# 11-de-7.net
KiCad netlist of a schematic drawn in EAGLE
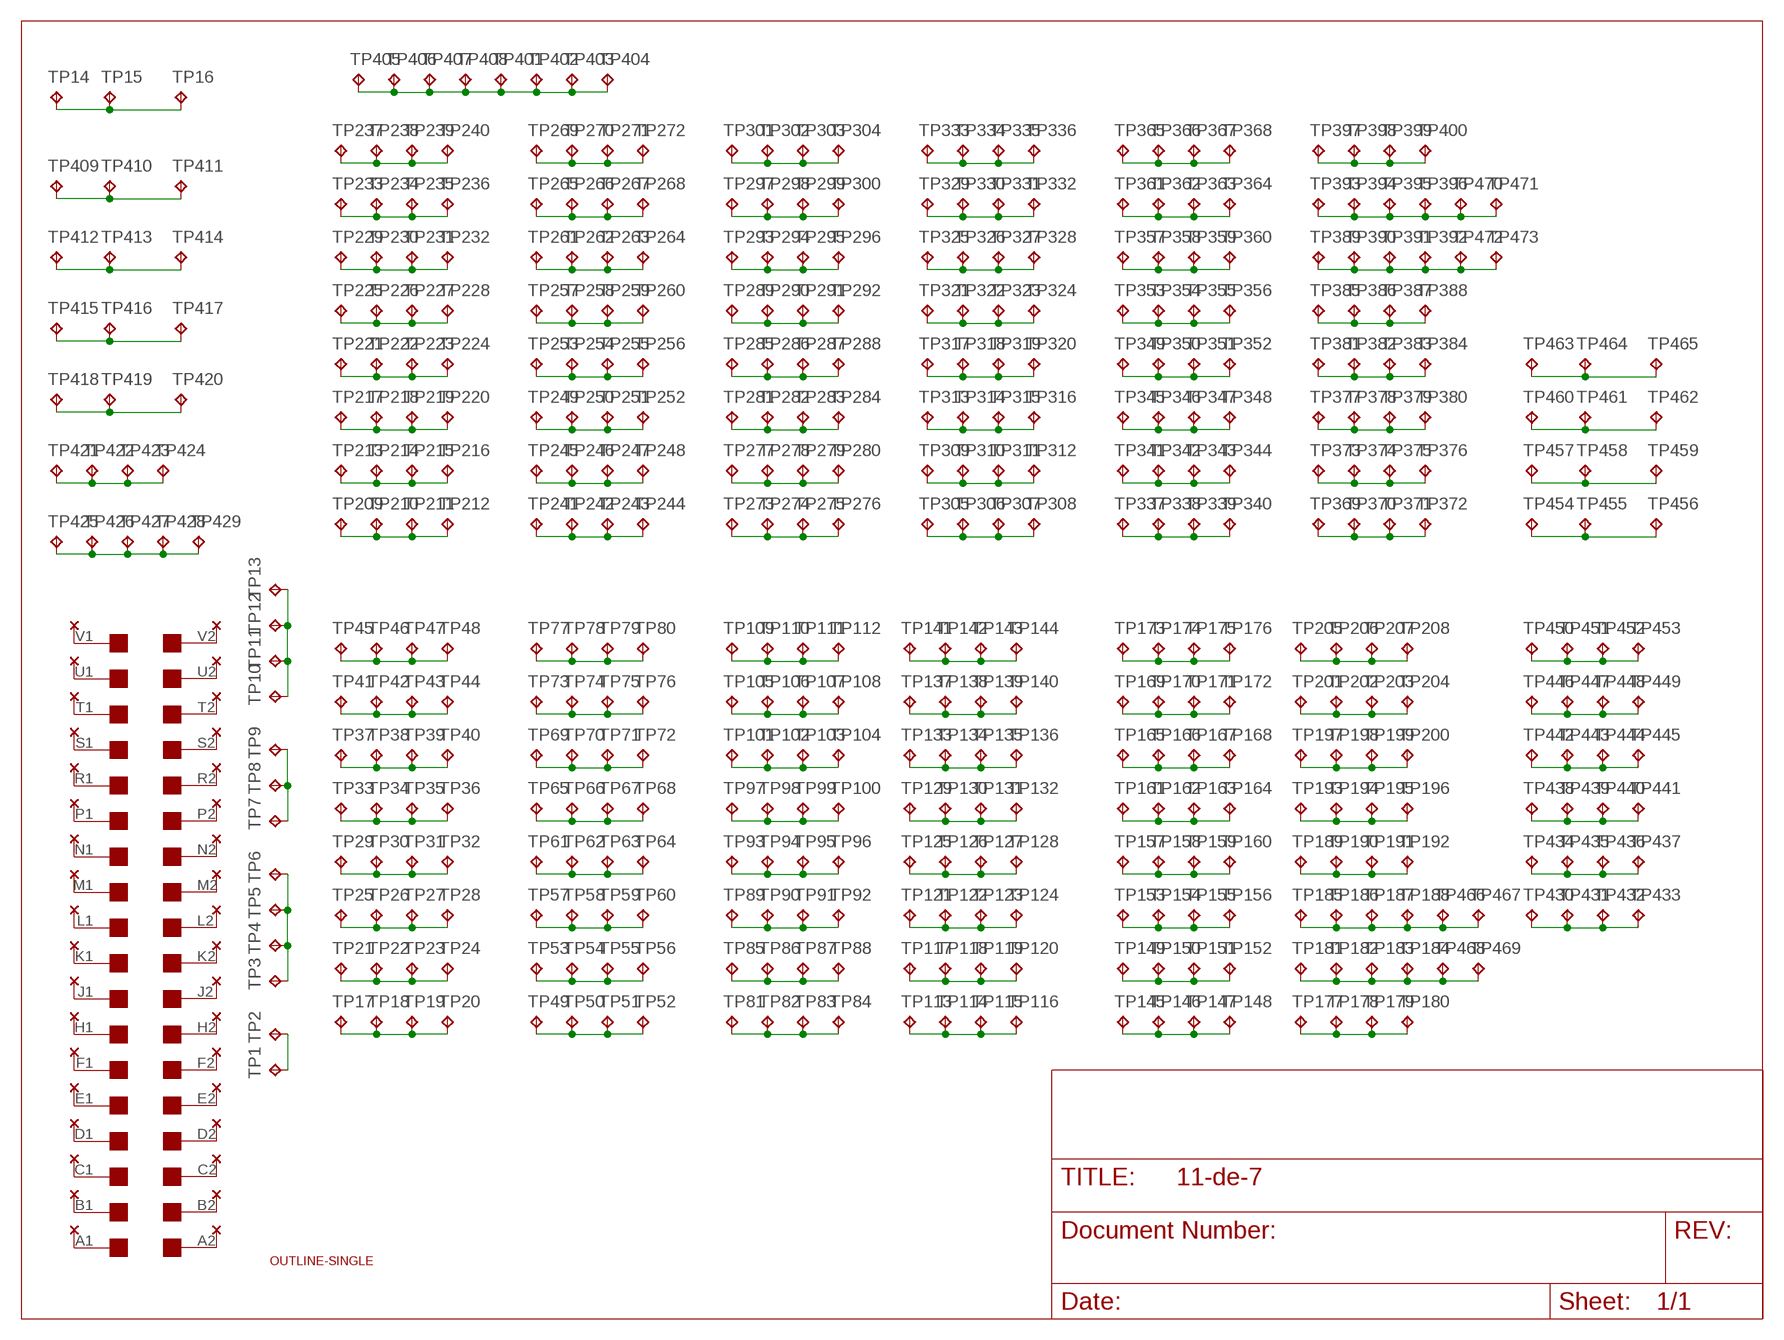
[diagram p0: schematic, sheet 1]

(export (version "E")
  (design (tool "Eeschema 10.0.6"))
  (components
    (comp (ref "TP1")
      (value "TPPAD1-13Y")
      (footprint "eagle-import:P1-13Y")
      (libsource (lib "eagle-import") (part "TPPAD1-13Y"))
    )
    (comp (ref "TP2")
      (value "TPPAD1-13")
      (footprint "eagle-import:P1-13")
      (libsource (lib "eagle-import") (part "TPPAD1-13"))
    )
    (comp (ref "TP3")
      (value "TPPAD1-13Y")
      (footprint "eagle-import:P1-13Y")
      (libsource (lib "eagle-import") (part "TPPAD1-13Y"))
    )
    (comp (ref "TP4")
      (value "TPPAD1-13Y")
      (footprint "eagle-import:P1-13Y")
      (libsource (lib "eagle-import") (part "TPPAD1-13Y"))
    )
    (comp (ref "TP5")
      (value "TPPAD1-13Y")
      (footprint "eagle-import:P1-13Y")
      (libsource (lib "eagle-import") (part "TPPAD1-13Y"))
    )
    (comp (ref "TP6")
      (value "TPPAD1-13Y")
      (footprint "eagle-import:P1-13Y")
      (libsource (lib "eagle-import") (part "TPPAD1-13Y"))
    )
    (comp (ref "TP7")
      (value "TPPAD1-13Y")
      (footprint "eagle-import:P1-13Y")
      (libsource (lib "eagle-import") (part "TPPAD1-13Y"))
    )
    (comp (ref "TP8")
      (value "TPPAD1-13Y")
      (footprint "eagle-import:P1-13Y")
      (libsource (lib "eagle-import") (part "TPPAD1-13Y"))
    )
    (comp (ref "TP9")
      (value "TPPAD1-13Y")
      (footprint "eagle-import:P1-13Y")
      (libsource (lib "eagle-import") (part "TPPAD1-13Y"))
    )
    (comp (ref "TP10")
      (value "TPPAD1-13Y")
      (footprint "eagle-import:P1-13Y")
      (libsource (lib "eagle-import") (part "TPPAD1-13Y"))
    )
    (comp (ref "TP11")
      (value "TPPAD1-13Y")
      (footprint "eagle-import:P1-13Y")
      (libsource (lib "eagle-import") (part "TPPAD1-13Y"))
    )
    (comp (ref "TP12")
      (value "TPPAD1-13Y")
      (footprint "eagle-import:P1-13Y")
      (libsource (lib "eagle-import") (part "TPPAD1-13Y"))
    )
    (comp (ref "TP13")
      (value "TPPAD1-13Y")
      (footprint "eagle-import:P1-13Y")
      (libsource (lib "eagle-import") (part "TPPAD1-13Y"))
    )
    (comp (ref "TP14")
      (value "TPPAD1-13Y")
      (footprint "eagle-import:P1-13Y")
      (libsource (lib "eagle-import") (part "TPPAD1-13Y"))
    )
    (comp (ref "TP15")
      (value "TPPAD1-13Y")
      (footprint "eagle-import:P1-13Y")
      (libsource (lib "eagle-import") (part "TPPAD1-13Y"))
    )
    (comp (ref "TP16")
      (value "TPPAD1-13Y")
      (footprint "eagle-import:P1-13Y")
      (libsource (lib "eagle-import") (part "TPPAD1-13Y"))
    )
    (comp (ref "TP17")
      (value "TPPAD1-13Y")
      (footprint "eagle-import:P1-13Y")
      (libsource (lib "eagle-import") (part "TPPAD1-13Y"))
    )
    (comp (ref "TP18")
      (value "TPPAD1-13Y")
      (footprint "eagle-import:P1-13Y")
      (libsource (lib "eagle-import") (part "TPPAD1-13Y"))
    )
    (comp (ref "TP19")
      (value "TPPAD1-13Y")
      (footprint "eagle-import:P1-13Y")
      (libsource (lib "eagle-import") (part "TPPAD1-13Y"))
    )
    (comp (ref "TP20")
      (value "TPPAD1-13Y")
      (footprint "eagle-import:P1-13Y")
      (libsource (lib "eagle-import") (part "TPPAD1-13Y"))
    )
    (comp (ref "TP21")
      (value "TPPAD1-13Y")
      (footprint "eagle-import:P1-13Y")
      (libsource (lib "eagle-import") (part "TPPAD1-13Y"))
    )
    (comp (ref "TP22")
      (value "TPPAD1-13Y")
      (footprint "eagle-import:P1-13Y")
      (libsource (lib "eagle-import") (part "TPPAD1-13Y"))
    )
    (comp (ref "TP23")
      (value "TPPAD1-13Y")
      (footprint "eagle-import:P1-13Y")
      (libsource (lib "eagle-import") (part "TPPAD1-13Y"))
    )
    (comp (ref "TP24")
      (value "TPPAD1-13Y")
      (footprint "eagle-import:P1-13Y")
      (libsource (lib "eagle-import") (part "TPPAD1-13Y"))
    )
    (comp (ref "TP25")
      (value "TPPAD1-13Y")
      (footprint "eagle-import:P1-13Y")
      (libsource (lib "eagle-import") (part "TPPAD1-13Y"))
    )
    (comp (ref "TP26")
      (value "TPPAD1-13Y")
      (footprint "eagle-import:P1-13Y")
      (libsource (lib "eagle-import") (part "TPPAD1-13Y"))
    )
    (comp (ref "TP27")
      (value "TPPAD1-13Y")
      (footprint "eagle-import:P1-13Y")
      (libsource (lib "eagle-import") (part "TPPAD1-13Y"))
    )
    (comp (ref "TP28")
      (value "TPPAD1-13Y")
      (footprint "eagle-import:P1-13Y")
      (libsource (lib "eagle-import") (part "TPPAD1-13Y"))
    )
    (comp (ref "TP29")
      (value "TPPAD1-13Y")
      (footprint "eagle-import:P1-13Y")
      (libsource (lib "eagle-import") (part "TPPAD1-13Y"))
    )
    (comp (ref "TP30")
      (value "TPPAD1-13Y")
      (footprint "eagle-import:P1-13Y")
      (libsource (lib "eagle-import") (part "TPPAD1-13Y"))
    )
    (comp (ref "TP31")
      (value "TPPAD1-13Y")
      (footprint "eagle-import:P1-13Y")
      (libsource (lib "eagle-import") (part "TPPAD1-13Y"))
    )
    (comp (ref "TP32")
      (value "TPPAD1-13Y")
      (footprint "eagle-import:P1-13Y")
      (libsource (lib "eagle-import") (part "TPPAD1-13Y"))
    )
    (comp (ref "TP33")
      (value "TPPAD1-13Y")
      (footprint "eagle-import:P1-13Y")
      (libsource (lib "eagle-import") (part "TPPAD1-13Y"))
    )
    (comp (ref "TP34")
      (value "TPPAD1-13Y")
      (footprint "eagle-import:P1-13Y")
      (libsource (lib "eagle-import") (part "TPPAD1-13Y"))
    )
    (comp (ref "TP35")
      (value "TPPAD1-13Y")
      (footprint "eagle-import:P1-13Y")
      (libsource (lib "eagle-import") (part "TPPAD1-13Y"))
    )
    (comp (ref "TP36")
      (value "TPPAD1-13Y")
      (footprint "eagle-import:P1-13Y")
      (libsource (lib "eagle-import") (part "TPPAD1-13Y"))
    )
    (comp (ref "TP37")
      (value "TPPAD1-13Y")
      (footprint "eagle-import:P1-13Y")
      (libsource (lib "eagle-import") (part "TPPAD1-13Y"))
    )
    (comp (ref "TP38")
      (value "TPPAD1-13Y")
      (footprint "eagle-import:P1-13Y")
      (libsource (lib "eagle-import") (part "TPPAD1-13Y"))
    )
    (comp (ref "TP39")
      (value "TPPAD1-13Y")
      (footprint "eagle-import:P1-13Y")
      (libsource (lib "eagle-import") (part "TPPAD1-13Y"))
    )
    (comp (ref "TP40")
      (value "TPPAD1-13Y")
      (footprint "eagle-import:P1-13Y")
      (libsource (lib "eagle-import") (part "TPPAD1-13Y"))
    )
    (comp (ref "TP41")
      (value "TPPAD1-13Y")
      (footprint "eagle-import:P1-13Y")
      (libsource (lib "eagle-import") (part "TPPAD1-13Y"))
    )
    (comp (ref "TP42")
      (value "TPPAD1-13Y")
      (footprint "eagle-import:P1-13Y")
      (libsource (lib "eagle-import") (part "TPPAD1-13Y"))
    )
    (comp (ref "TP43")
      (value "TPPAD1-13Y")
      (footprint "eagle-import:P1-13Y")
      (libsource (lib "eagle-import") (part "TPPAD1-13Y"))
    )
    (comp (ref "TP44")
      (value "TPPAD1-13Y")
      (footprint "eagle-import:P1-13Y")
      (libsource (lib "eagle-import") (part "TPPAD1-13Y"))
    )
    (comp (ref "TP45")
      (value "TPPAD1-13Y")
      (footprint "eagle-import:P1-13Y")
      (libsource (lib "eagle-import") (part "TPPAD1-13Y"))
    )
    (comp (ref "TP46")
      (value "TPPAD1-13Y")
      (footprint "eagle-import:P1-13Y")
      (libsource (lib "eagle-import") (part "TPPAD1-13Y"))
    )
    (comp (ref "TP47")
      (value "TPPAD1-13Y")
      (footprint "eagle-import:P1-13Y")
      (libsource (lib "eagle-import") (part "TPPAD1-13Y"))
    )
    (comp (ref "TP48")
      (value "TPPAD1-13Y")
      (footprint "eagle-import:P1-13Y")
      (libsource (lib "eagle-import") (part "TPPAD1-13Y"))
    )
    (comp (ref "TP49")
      (value "TPPAD1-13Y")
      (footprint "eagle-import:P1-13Y")
      (libsource (lib "eagle-import") (part "TPPAD1-13Y"))
    )
    (comp (ref "TP50")
      (value "TPPAD1-13Y")
      (footprint "eagle-import:P1-13Y")
      (libsource (lib "eagle-import") (part "TPPAD1-13Y"))
    )
    (comp (ref "TP51")
      (value "TPPAD1-13Y")
      (footprint "eagle-import:P1-13Y")
      (libsource (lib "eagle-import") (part "TPPAD1-13Y"))
    )
    (comp (ref "TP52")
      (value "TPPAD1-13Y")
      (footprint "eagle-import:P1-13Y")
      (libsource (lib "eagle-import") (part "TPPAD1-13Y"))
    )
    (comp (ref "TP53")
      (value "TPPAD1-13Y")
      (footprint "eagle-import:P1-13Y")
      (libsource (lib "eagle-import") (part "TPPAD1-13Y"))
    )
    (comp (ref "TP54")
      (value "TPPAD1-13Y")
      (footprint "eagle-import:P1-13Y")
      (libsource (lib "eagle-import") (part "TPPAD1-13Y"))
    )
    (comp (ref "TP55")
      (value "TPPAD1-13Y")
      (footprint "eagle-import:P1-13Y")
      (libsource (lib "eagle-import") (part "TPPAD1-13Y"))
    )
    (comp (ref "TP56")
      (value "TPPAD1-13Y")
      (footprint "eagle-import:P1-13Y")
      (libsource (lib "eagle-import") (part "TPPAD1-13Y"))
    )
    (comp (ref "TP57")
      (value "TPPAD1-13Y")
      (footprint "eagle-import:P1-13Y")
      (libsource (lib "eagle-import") (part "TPPAD1-13Y"))
    )
    (comp (ref "TP58")
      (value "TPPAD1-13Y")
      (footprint "eagle-import:P1-13Y")
      (libsource (lib "eagle-import") (part "TPPAD1-13Y"))
    )
    (comp (ref "TP59")
      (value "TPPAD1-13Y")
      (footprint "eagle-import:P1-13Y")
      (libsource (lib "eagle-import") (part "TPPAD1-13Y"))
    )
    (comp (ref "TP60")
      (value "TPPAD1-13Y")
      (footprint "eagle-import:P1-13Y")
      (libsource (lib "eagle-import") (part "TPPAD1-13Y"))
    )
    (comp (ref "TP61")
      (value "TPPAD1-13Y")
      (footprint "eagle-import:P1-13Y")
      (libsource (lib "eagle-import") (part "TPPAD1-13Y"))
    )
    (comp (ref "TP62")
      (value "TPPAD1-13Y")
      (footprint "eagle-import:P1-13Y")
      (libsource (lib "eagle-import") (part "TPPAD1-13Y"))
    )
    (comp (ref "TP63")
      (value "TPPAD1-13Y")
      (footprint "eagle-import:P1-13Y")
      (libsource (lib "eagle-import") (part "TPPAD1-13Y"))
    )
    (comp (ref "TP64")
      (value "TPPAD1-13Y")
      (footprint "eagle-import:P1-13Y")
      (libsource (lib "eagle-import") (part "TPPAD1-13Y"))
    )
    (comp (ref "TP65")
      (value "TPPAD1-13Y")
      (footprint "eagle-import:P1-13Y")
      (libsource (lib "eagle-import") (part "TPPAD1-13Y"))
    )
    (comp (ref "TP66")
      (value "TPPAD1-13Y")
      (footprint "eagle-import:P1-13Y")
      (libsource (lib "eagle-import") (part "TPPAD1-13Y"))
    )
    (comp (ref "TP67")
      (value "TPPAD1-13Y")
      (footprint "eagle-import:P1-13Y")
      (libsource (lib "eagle-import") (part "TPPAD1-13Y"))
    )
    (comp (ref "TP68")
      (value "TPPAD1-13Y")
      (footprint "eagle-import:P1-13Y")
      (libsource (lib "eagle-import") (part "TPPAD1-13Y"))
    )
    (comp (ref "TP69")
      (value "TPPAD1-13Y")
      (footprint "eagle-import:P1-13Y")
      (libsource (lib "eagle-import") (part "TPPAD1-13Y"))
    )
    (comp (ref "TP70")
      (value "TPPAD1-13Y")
      (footprint "eagle-import:P1-13Y")
      (libsource (lib "eagle-import") (part "TPPAD1-13Y"))
    )
    (comp (ref "TP71")
      (value "TPPAD1-13Y")
      (footprint "eagle-import:P1-13Y")
      (libsource (lib "eagle-import") (part "TPPAD1-13Y"))
    )
    (comp (ref "TP72")
      (value "TPPAD1-13Y")
      (footprint "eagle-import:P1-13Y")
      (libsource (lib "eagle-import") (part "TPPAD1-13Y"))
    )
    (comp (ref "TP73")
      (value "TPPAD1-13Y")
      (footprint "eagle-import:P1-13Y")
      (libsource (lib "eagle-import") (part "TPPAD1-13Y"))
    )
    (comp (ref "TP74")
      (value "TPPAD1-13Y")
      (footprint "eagle-import:P1-13Y")
      (libsource (lib "eagle-import") (part "TPPAD1-13Y"))
    )
    (comp (ref "TP75")
      (value "TPPAD1-13Y")
      (footprint "eagle-import:P1-13Y")
      (libsource (lib "eagle-import") (part "TPPAD1-13Y"))
    )
    (comp (ref "TP76")
      (value "TPPAD1-13Y")
      (footprint "eagle-import:P1-13Y")
      (libsource (lib "eagle-import") (part "TPPAD1-13Y"))
    )
    (comp (ref "TP77")
      (value "TPPAD1-13Y")
      (footprint "eagle-import:P1-13Y")
      (libsource (lib "eagle-import") (part "TPPAD1-13Y"))
    )
    (comp (ref "TP78")
      (value "TPPAD1-13Y")
      (footprint "eagle-import:P1-13Y")
      (libsource (lib "eagle-import") (part "TPPAD1-13Y"))
    )
    (comp (ref "TP79")
      (value "TPPAD1-13Y")
      (footprint "eagle-import:P1-13Y")
      (libsource (lib "eagle-import") (part "TPPAD1-13Y"))
    )
    (comp (ref "TP80")
      (value "TPPAD1-13Y")
      (footprint "eagle-import:P1-13Y")
      (libsource (lib "eagle-import") (part "TPPAD1-13Y"))
    )
    (comp (ref "TP81")
      (value "TPPAD1-13Y")
      (footprint "eagle-import:P1-13Y")
      (libsource (lib "eagle-import") (part "TPPAD1-13Y"))
    )
    (comp (ref "TP82")
      (value "TPPAD1-13Y")
      (footprint "eagle-import:P1-13Y")
      (libsource (lib "eagle-import") (part "TPPAD1-13Y"))
    )
    (comp (ref "TP83")
      (value "TPPAD1-13Y")
      (footprint "eagle-import:P1-13Y")
      (libsource (lib "eagle-import") (part "TPPAD1-13Y"))
    )
    (comp (ref "TP84")
      (value "TPPAD1-13Y")
      (footprint "eagle-import:P1-13Y")
      (libsource (lib "eagle-import") (part "TPPAD1-13Y"))
    )
    (comp (ref "TP85")
      (value "TPPAD1-13Y")
      (footprint "eagle-import:P1-13Y")
      (libsource (lib "eagle-import") (part "TPPAD1-13Y"))
    )
    (comp (ref "TP86")
      (value "TPPAD1-13Y")
      (footprint "eagle-import:P1-13Y")
      (libsource (lib "eagle-import") (part "TPPAD1-13Y"))
    )
    (comp (ref "TP87")
      (value "TPPAD1-13Y")
      (footprint "eagle-import:P1-13Y")
      (libsource (lib "eagle-import") (part "TPPAD1-13Y"))
    )
    (comp (ref "TP88")
      (value "TPPAD1-13Y")
      (footprint "eagle-import:P1-13Y")
      (libsource (lib "eagle-import") (part "TPPAD1-13Y"))
    )
    (comp (ref "TP89")
      (value "TPPAD1-13Y")
      (footprint "eagle-import:P1-13Y")
      (libsource (lib "eagle-import") (part "TPPAD1-13Y"))
    )
    (comp (ref "TP90")
      (value "TPPAD1-13Y")
      (footprint "eagle-import:P1-13Y")
      (libsource (lib "eagle-import") (part "TPPAD1-13Y"))
    )
    (comp (ref "TP91")
      (value "TPPAD1-13Y")
      (footprint "eagle-import:P1-13Y")
      (libsource (lib "eagle-import") (part "TPPAD1-13Y"))
    )
    (comp (ref "TP92")
      (value "TPPAD1-13Y")
      (footprint "eagle-import:P1-13Y")
      (libsource (lib "eagle-import") (part "TPPAD1-13Y"))
    )
    (comp (ref "TP93")
      (value "TPPAD1-13Y")
      (footprint "eagle-import:P1-13Y")
      (libsource (lib "eagle-import") (part "TPPAD1-13Y"))
    )
    (comp (ref "TP94")
      (value "TPPAD1-13Y")
      (footprint "eagle-import:P1-13Y")
      (libsource (lib "eagle-import") (part "TPPAD1-13Y"))
    )
    (comp (ref "TP95")
      (value "TPPAD1-13Y")
      (footprint "eagle-import:P1-13Y")
      (libsource (lib "eagle-import") (part "TPPAD1-13Y"))
    )
    (comp (ref "TP96")
      (value "TPPAD1-13Y")
      (footprint "eagle-import:P1-13Y")
      (libsource (lib "eagle-import") (part "TPPAD1-13Y"))
    )
    (comp (ref "TP97")
      (value "TPPAD1-13Y")
      (footprint "eagle-import:P1-13Y")
      (libsource (lib "eagle-import") (part "TPPAD1-13Y"))
    )
    (comp (ref "TP98")
      (value "TPPAD1-13Y")
      (footprint "eagle-import:P1-13Y")
      (libsource (lib "eagle-import") (part "TPPAD1-13Y"))
    )
    (comp (ref "TP99")
      (value "TPPAD1-13Y")
      (footprint "eagle-import:P1-13Y")
      (libsource (lib "eagle-import") (part "TPPAD1-13Y"))
    )
    (comp (ref "TP100")
      (value "TPPAD1-13Y")
      (footprint "eagle-import:P1-13Y")
      (libsource (lib "eagle-import") (part "TPPAD1-13Y"))
    )
    (comp (ref "TP101")
      (value "TPPAD1-13Y")
      (footprint "eagle-import:P1-13Y")
      (libsource (lib "eagle-import") (part "TPPAD1-13Y"))
    )
    (comp (ref "TP102")
      (value "TPPAD1-13Y")
      (footprint "eagle-import:P1-13Y")
      (libsource (lib "eagle-import") (part "TPPAD1-13Y"))
    )
    (comp (ref "TP103")
      (value "TPPAD1-13Y")
      (footprint "eagle-import:P1-13Y")
      (libsource (lib "eagle-import") (part "TPPAD1-13Y"))
    )
    (comp (ref "TP104")
      (value "TPPAD1-13Y")
      (footprint "eagle-import:P1-13Y")
      (libsource (lib "eagle-import") (part "TPPAD1-13Y"))
    )
    (comp (ref "TP105")
      (value "TPPAD1-13Y")
      (footprint "eagle-import:P1-13Y")
      (libsource (lib "eagle-import") (part "TPPAD1-13Y"))
    )
    (comp (ref "TP106")
      (value "TPPAD1-13Y")
      (footprint "eagle-import:P1-13Y")
      (libsource (lib "eagle-import") (part "TPPAD1-13Y"))
    )
    (comp (ref "TP107")
      (value "TPPAD1-13Y")
      (footprint "eagle-import:P1-13Y")
      (libsource (lib "eagle-import") (part "TPPAD1-13Y"))
    )
    (comp (ref "TP108")
      (value "TPPAD1-13Y")
      (footprint "eagle-import:P1-13Y")
      (libsource (lib "eagle-import") (part "TPPAD1-13Y"))
    )
    (comp (ref "TP109")
      (value "TPPAD1-13Y")
      (footprint "eagle-import:P1-13Y")
      (libsource (lib "eagle-import") (part "TPPAD1-13Y"))
    )
    (comp (ref "TP110")
      (value "TPPAD1-13Y")
      (footprint "eagle-import:P1-13Y")
      (libsource (lib "eagle-import") (part "TPPAD1-13Y"))
    )
    (comp (ref "TP111")
      (value "TPPAD1-13Y")
      (footprint "eagle-import:P1-13Y")
      (libsource (lib "eagle-import") (part "TPPAD1-13Y"))
    )
    (comp (ref "TP112")
      (value "TPPAD1-13Y")
      (footprint "eagle-import:P1-13Y")
      (libsource (lib "eagle-import") (part "TPPAD1-13Y"))
    )
    (comp (ref "TP113")
      (value "TPPAD1-13Y")
      (footprint "eagle-import:P1-13Y")
      (libsource (lib "eagle-import") (part "TPPAD1-13Y"))
    )
    (comp (ref "TP114")
      (value "TPPAD1-13Y")
      (footprint "eagle-import:P1-13Y")
      (libsource (lib "eagle-import") (part "TPPAD1-13Y"))
    )
    (comp (ref "TP115")
      (value "TPPAD1-13Y")
      (footprint "eagle-import:P1-13Y")
      (libsource (lib "eagle-import") (part "TPPAD1-13Y"))
    )
    (comp (ref "TP116")
      (value "TPPAD1-13Y")
      (footprint "eagle-import:P1-13Y")
      (libsource (lib "eagle-import") (part "TPPAD1-13Y"))
    )
    (comp (ref "TP117")
      (value "TPPAD1-13Y")
      (footprint "eagle-import:P1-13Y")
      (libsource (lib "eagle-import") (part "TPPAD1-13Y"))
    )
    (comp (ref "TP118")
      (value "TPPAD1-13Y")
      (footprint "eagle-import:P1-13Y")
      (libsource (lib "eagle-import") (part "TPPAD1-13Y"))
    )
    (comp (ref "TP119")
      (value "TPPAD1-13Y")
      (footprint "eagle-import:P1-13Y")
      (libsource (lib "eagle-import") (part "TPPAD1-13Y"))
    )
    (comp (ref "TP120")
      (value "TPPAD1-13Y")
      (footprint "eagle-import:P1-13Y")
      (libsource (lib "eagle-import") (part "TPPAD1-13Y"))
    )
    (comp (ref "TP121")
      (value "TPPAD1-13Y")
      (footprint "eagle-import:P1-13Y")
      (libsource (lib "eagle-import") (part "TPPAD1-13Y"))
    )
    (comp (ref "TP122")
      (value "TPPAD1-13Y")
      (footprint "eagle-import:P1-13Y")
      (libsource (lib "eagle-import") (part "TPPAD1-13Y"))
    )
    (comp (ref "TP123")
      (value "TPPAD1-13Y")
      (footprint "eagle-import:P1-13Y")
      (libsource (lib "eagle-import") (part "TPPAD1-13Y"))
    )
    (comp (ref "TP124")
      (value "TPPAD1-13Y")
      (footprint "eagle-import:P1-13Y")
      (libsource (lib "eagle-import") (part "TPPAD1-13Y"))
    )
    (comp (ref "TP125")
      (value "TPPAD1-13Y")
      (footprint "eagle-import:P1-13Y")
      (libsource (lib "eagle-import") (part "TPPAD1-13Y"))
    )
    (comp (ref "TP126")
      (value "TPPAD1-13Y")
      (footprint "eagle-import:P1-13Y")
      (libsource (lib "eagle-import") (part "TPPAD1-13Y"))
    )
    (comp (ref "TP127")
      (value "TPPAD1-13Y")
      (footprint "eagle-import:P1-13Y")
      (libsource (lib "eagle-import") (part "TPPAD1-13Y"))
    )
    (comp (ref "TP128")
      (value "TPPAD1-13Y")
      (footprint "eagle-import:P1-13Y")
      (libsource (lib "eagle-import") (part "TPPAD1-13Y"))
    )
    (comp (ref "TP129")
      (value "TPPAD1-13Y")
      (footprint "eagle-import:P1-13Y")
      (libsource (lib "eagle-import") (part "TPPAD1-13Y"))
    )
    (comp (ref "TP130")
      (value "TPPAD1-13Y")
      (footprint "eagle-import:P1-13Y")
      (libsource (lib "eagle-import") (part "TPPAD1-13Y"))
    )
    (comp (ref "TP131")
      (value "TPPAD1-13Y")
      (footprint "eagle-import:P1-13Y")
      (libsource (lib "eagle-import") (part "TPPAD1-13Y"))
    )
    (comp (ref "TP132")
      (value "TPPAD1-13Y")
      (footprint "eagle-import:P1-13Y")
      (libsource (lib "eagle-import") (part "TPPAD1-13Y"))
    )
    (comp (ref "TP133")
      (value "TPPAD1-13Y")
      (footprint "eagle-import:P1-13Y")
      (libsource (lib "eagle-import") (part "TPPAD1-13Y"))
    )
    (comp (ref "TP134")
      (value "TPPAD1-13Y")
      (footprint "eagle-import:P1-13Y")
      (libsource (lib "eagle-import") (part "TPPAD1-13Y"))
    )
    (comp (ref "TP135")
      (value "TPPAD1-13Y")
      (footprint "eagle-import:P1-13Y")
      (libsource (lib "eagle-import") (part "TPPAD1-13Y"))
    )
    (comp (ref "TP136")
      (value "TPPAD1-13Y")
      (footprint "eagle-import:P1-13Y")
      (libsource (lib "eagle-import") (part "TPPAD1-13Y"))
    )
    (comp (ref "TP137")
      (value "TPPAD1-13Y")
      (footprint "eagle-import:P1-13Y")
      (libsource (lib "eagle-import") (part "TPPAD1-13Y"))
    )
    (comp (ref "TP138")
      (value "TPPAD1-13Y")
      (footprint "eagle-import:P1-13Y")
      (libsource (lib "eagle-import") (part "TPPAD1-13Y"))
    )
    (comp (ref "TP139")
      (value "TPPAD1-13Y")
      (footprint "eagle-import:P1-13Y")
      (libsource (lib "eagle-import") (part "TPPAD1-13Y"))
    )
    (comp (ref "TP140")
      (value "TPPAD1-13Y")
      (footprint "eagle-import:P1-13Y")
      (libsource (lib "eagle-import") (part "TPPAD1-13Y"))
    )
    (comp (ref "TP141")
      (value "TPPAD1-13Y")
      (footprint "eagle-import:P1-13Y")
      (libsource (lib "eagle-import") (part "TPPAD1-13Y"))
    )
    (comp (ref "TP142")
      (value "TPPAD1-13Y")
      (footprint "eagle-import:P1-13Y")
      (libsource (lib "eagle-import") (part "TPPAD1-13Y"))
    )
    (comp (ref "TP143")
      (value "TPPAD1-13Y")
      (footprint "eagle-import:P1-13Y")
      (libsource (lib "eagle-import") (part "TPPAD1-13Y"))
    )
    (comp (ref "TP144")
      (value "TPPAD1-13Y")
      (footprint "eagle-import:P1-13Y")
      (libsource (lib "eagle-import") (part "TPPAD1-13Y"))
    )
    (comp (ref "TP145")
      (value "TPPAD1-13Y")
      (footprint "eagle-import:P1-13Y")
      (libsource (lib "eagle-import") (part "TPPAD1-13Y"))
    )
    (comp (ref "TP146")
      (value "TPPAD1-13Y")
      (footprint "eagle-import:P1-13Y")
      (libsource (lib "eagle-import") (part "TPPAD1-13Y"))
    )
    (comp (ref "TP147")
      (value "TPPAD1-13Y")
      (footprint "eagle-import:P1-13Y")
      (libsource (lib "eagle-import") (part "TPPAD1-13Y"))
    )
    (comp (ref "TP148")
      (value "TPPAD1-13Y")
      (footprint "eagle-import:P1-13Y")
      (libsource (lib "eagle-import") (part "TPPAD1-13Y"))
    )
    (comp (ref "TP149")
      (value "TPPAD1-13Y")
      (footprint "eagle-import:P1-13Y")
      (libsource (lib "eagle-import") (part "TPPAD1-13Y"))
    )
    (comp (ref "TP150")
      (value "TPPAD1-13Y")
      (footprint "eagle-import:P1-13Y")
      (libsource (lib "eagle-import") (part "TPPAD1-13Y"))
    )
    (comp (ref "TP151")
      (value "TPPAD1-13Y")
      (footprint "eagle-import:P1-13Y")
      (libsource (lib "eagle-import") (part "TPPAD1-13Y"))
    )
    (comp (ref "TP152")
      (value "TPPAD1-13Y")
      (footprint "eagle-import:P1-13Y")
      (libsource (lib "eagle-import") (part "TPPAD1-13Y"))
    )
    (comp (ref "TP153")
      (value "TPPAD1-13Y")
      (footprint "eagle-import:P1-13Y")
      (libsource (lib "eagle-import") (part "TPPAD1-13Y"))
    )
    (comp (ref "TP154")
      (value "TPPAD1-13Y")
      (footprint "eagle-import:P1-13Y")
      (libsource (lib "eagle-import") (part "TPPAD1-13Y"))
    )
    (comp (ref "TP155")
      (value "TPPAD1-13Y")
      (footprint "eagle-import:P1-13Y")
      (libsource (lib "eagle-import") (part "TPPAD1-13Y"))
    )
    (comp (ref "TP156")
      (value "TPPAD1-13Y")
      (footprint "eagle-import:P1-13Y")
      (libsource (lib "eagle-import") (part "TPPAD1-13Y"))
    )
    (comp (ref "TP157")
      (value "TPPAD1-13Y")
      (footprint "eagle-import:P1-13Y")
      (libsource (lib "eagle-import") (part "TPPAD1-13Y"))
    )
    (comp (ref "TP158")
      (value "TPPAD1-13Y")
      (footprint "eagle-import:P1-13Y")
      (libsource (lib "eagle-import") (part "TPPAD1-13Y"))
    )
    (comp (ref "TP159")
      (value "TPPAD1-13Y")
      (footprint "eagle-import:P1-13Y")
      (libsource (lib "eagle-import") (part "TPPAD1-13Y"))
    )
    (comp (ref "TP160")
      (value "TPPAD1-13Y")
      (footprint "eagle-import:P1-13Y")
      (libsource (lib "eagle-import") (part "TPPAD1-13Y"))
    )
    (comp (ref "TP161")
      (value "TPPAD1-13Y")
      (footprint "eagle-import:P1-13Y")
      (libsource (lib "eagle-import") (part "TPPAD1-13Y"))
    )
    (comp (ref "TP162")
      (value "TPPAD1-13Y")
      (footprint "eagle-import:P1-13Y")
      (libsource (lib "eagle-import") (part "TPPAD1-13Y"))
    )
    (comp (ref "TP163")
      (value "TPPAD1-13Y")
      (footprint "eagle-import:P1-13Y")
      (libsource (lib "eagle-import") (part "TPPAD1-13Y"))
    )
    (comp (ref "TP164")
      (value "TPPAD1-13Y")
      (footprint "eagle-import:P1-13Y")
      (libsource (lib "eagle-import") (part "TPPAD1-13Y"))
    )
    (comp (ref "TP165")
      (value "TPPAD1-13Y")
      (footprint "eagle-import:P1-13Y")
      (libsource (lib "eagle-import") (part "TPPAD1-13Y"))
    )
    (comp (ref "TP166")
      (value "TPPAD1-13Y")
      (footprint "eagle-import:P1-13Y")
      (libsource (lib "eagle-import") (part "TPPAD1-13Y"))
    )
    (comp (ref "TP167")
      (value "TPPAD1-13Y")
      (footprint "eagle-import:P1-13Y")
      (libsource (lib "eagle-import") (part "TPPAD1-13Y"))
    )
    (comp (ref "TP168")
      (value "TPPAD1-13Y")
      (footprint "eagle-import:P1-13Y")
      (libsource (lib "eagle-import") (part "TPPAD1-13Y"))
    )
    (comp (ref "TP169")
      (value "TPPAD1-13Y")
      (footprint "eagle-import:P1-13Y")
      (libsource (lib "eagle-import") (part "TPPAD1-13Y"))
    )
    (comp (ref "TP170")
      (value "TPPAD1-13Y")
      (footprint "eagle-import:P1-13Y")
      (libsource (lib "eagle-import") (part "TPPAD1-13Y"))
    )
    (comp (ref "TP171")
      (value "TPPAD1-13Y")
      (footprint "eagle-import:P1-13Y")
      (libsource (lib "eagle-import") (part "TPPAD1-13Y"))
    )
    (comp (ref "TP172")
      (value "TPPAD1-13Y")
      (footprint "eagle-import:P1-13Y")
      (libsource (lib "eagle-import") (part "TPPAD1-13Y"))
    )
    (comp (ref "TP173")
      (value "TPPAD1-13Y")
      (footprint "eagle-import:P1-13Y")
      (libsource (lib "eagle-import") (part "TPPAD1-13Y"))
    )
    (comp (ref "TP174")
      (value "TPPAD1-13Y")
      (footprint "eagle-import:P1-13Y")
      (libsource (lib "eagle-import") (part "TPPAD1-13Y"))
    )
    (comp (ref "TP175")
      (value "TPPAD1-13Y")
      (footprint "eagle-import:P1-13Y")
      (libsource (lib "eagle-import") (part "TPPAD1-13Y"))
    )
    (comp (ref "TP176")
      (value "TPPAD1-13Y")
      (footprint "eagle-import:P1-13Y")
      (libsource (lib "eagle-import") (part "TPPAD1-13Y"))
    )
    (comp (ref "TP177")
      (value "TPPAD1-13Y")
      (footprint "eagle-import:P1-13Y")
      (libsource (lib "eagle-import") (part "TPPAD1-13Y"))
    )
    (comp (ref "TP178")
      (value "TPPAD1-13Y")
      (footprint "eagle-import:P1-13Y")
      (libsource (lib "eagle-import") (part "TPPAD1-13Y"))
    )
    (comp (ref "TP179")
      (value "TPPAD1-13Y")
      (footprint "eagle-import:P1-13Y")
      (libsource (lib "eagle-import") (part "TPPAD1-13Y"))
    )
    (comp (ref "TP180")
      (value "TPPAD1-13Y")
      (footprint "eagle-import:P1-13Y")
      (libsource (lib "eagle-import") (part "TPPAD1-13Y"))
    )
    (comp (ref "TP181")
      (value "TPPAD1-13Y")
      (footprint "eagle-import:P1-13Y")
      (libsource (lib "eagle-import") (part "TPPAD1-13Y"))
    )
    (comp (ref "TP182")
      (value "TPPAD1-13Y")
      (footprint "eagle-import:P1-13Y")
      (libsource (lib "eagle-import") (part "TPPAD1-13Y"))
    )
    (comp (ref "TP183")
      (value "TPPAD1-13Y")
      (footprint "eagle-import:P1-13Y")
      (libsource (lib "eagle-import") (part "TPPAD1-13Y"))
    )
    (comp (ref "TP184")
      (value "TPPAD1-13Y")
      (footprint "eagle-import:P1-13Y")
      (libsource (lib "eagle-import") (part "TPPAD1-13Y"))
    )
    (comp (ref "TP185")
      (value "TPPAD1-13Y")
      (footprint "eagle-import:P1-13Y")
      (libsource (lib "eagle-import") (part "TPPAD1-13Y"))
    )
    (comp (ref "TP186")
      (value "TPPAD1-13Y")
      (footprint "eagle-import:P1-13Y")
      (libsource (lib "eagle-import") (part "TPPAD1-13Y"))
    )
    (comp (ref "TP187")
      (value "TPPAD1-13Y")
      (footprint "eagle-import:P1-13Y")
      (libsource (lib "eagle-import") (part "TPPAD1-13Y"))
    )
    (comp (ref "TP188")
      (value "TPPAD1-13Y")
      (footprint "eagle-import:P1-13Y")
      (libsource (lib "eagle-import") (part "TPPAD1-13Y"))
    )
    (comp (ref "TP189")
      (value "TPPAD1-13Y")
      (footprint "eagle-import:P1-13Y")
      (libsource (lib "eagle-import") (part "TPPAD1-13Y"))
    )
    (comp (ref "TP190")
      (value "TPPAD1-13Y")
      (footprint "eagle-import:P1-13Y")
      (libsource (lib "eagle-import") (part "TPPAD1-13Y"))
    )
    (comp (ref "TP191")
      (value "TPPAD1-13Y")
      (footprint "eagle-import:P1-13Y")
      (libsource (lib "eagle-import") (part "TPPAD1-13Y"))
    )
    (comp (ref "TP192")
      (value "TPPAD1-13Y")
      (footprint "eagle-import:P1-13Y")
      (libsource (lib "eagle-import") (part "TPPAD1-13Y"))
    )
    (comp (ref "TP193")
      (value "TPPAD1-13Y")
      (footprint "eagle-import:P1-13Y")
      (libsource (lib "eagle-import") (part "TPPAD1-13Y"))
    )
    (comp (ref "TP194")
      (value "TPPAD1-13Y")
      (footprint "eagle-import:P1-13Y")
      (libsource (lib "eagle-import") (part "TPPAD1-13Y"))
    )
    (comp (ref "TP195")
      (value "TPPAD1-13Y")
      (footprint "eagle-import:P1-13Y")
      (libsource (lib "eagle-import") (part "TPPAD1-13Y"))
    )
    (comp (ref "TP196")
      (value "TPPAD1-13Y")
      (footprint "eagle-import:P1-13Y")
      (libsource (lib "eagle-import") (part "TPPAD1-13Y"))
    )
    (comp (ref "TP197")
      (value "TPPAD1-13Y")
      (footprint "eagle-import:P1-13Y")
      (libsource (lib "eagle-import") (part "TPPAD1-13Y"))
    )
    (comp (ref "TP198")
      (value "TPPAD1-13Y")
      (footprint "eagle-import:P1-13Y")
      (libsource (lib "eagle-import") (part "TPPAD1-13Y"))
    )
    (comp (ref "TP199")
      (value "TPPAD1-13Y")
      (footprint "eagle-import:P1-13Y")
      (libsource (lib "eagle-import") (part "TPPAD1-13Y"))
    )
    (comp (ref "TP200")
      (value "TPPAD1-13Y")
      (footprint "eagle-import:P1-13Y")
      (libsource (lib "eagle-import") (part "TPPAD1-13Y"))
    )
    (comp (ref "TP201")
      (value "TPPAD1-13Y")
      (footprint "eagle-import:P1-13Y")
      (libsource (lib "eagle-import") (part "TPPAD1-13Y"))
    )
    (comp (ref "TP202")
      (value "TPPAD1-13Y")
      (footprint "eagle-import:P1-13Y")
      (libsource (lib "eagle-import") (part "TPPAD1-13Y"))
    )
    (comp (ref "TP203")
      (value "TPPAD1-13Y")
      (footprint "eagle-import:P1-13Y")
      (libsource (lib "eagle-import") (part "TPPAD1-13Y"))
    )
    (comp (ref "TP204")
      (value "TPPAD1-13Y")
      (footprint "eagle-import:P1-13Y")
      (libsource (lib "eagle-import") (part "TPPAD1-13Y"))
    )
    (comp (ref "TP205")
      (value "TPPAD1-13Y")
      (footprint "eagle-import:P1-13Y")
      (libsource (lib "eagle-import") (part "TPPAD1-13Y"))
    )
    (comp (ref "TP206")
      (value "TPPAD1-13Y")
      (footprint "eagle-import:P1-13Y")
      (libsource (lib "eagle-import") (part "TPPAD1-13Y"))
    )
    (comp (ref "TP207")
      (value "TPPAD1-13Y")
      (footprint "eagle-import:P1-13Y")
      (libsource (lib "eagle-import") (part "TPPAD1-13Y"))
    )
    (comp (ref "TP208")
      (value "TPPAD1-13Y")
      (footprint "eagle-import:P1-13Y")
      (libsource (lib "eagle-import") (part "TPPAD1-13Y"))
    )
    (comp (ref "TP209")
      (value "TPPAD1-13Y")
      (footprint "eagle-import:P1-13Y")
      (libsource (lib "eagle-import") (part "TPPAD1-13Y"))
    )
    (comp (ref "TP210")
      (value "TPPAD1-13Y")
      (footprint "eagle-import:P1-13Y")
      (libsource (lib "eagle-import") (part "TPPAD1-13Y"))
    )
    (comp (ref "TP211")
      (value "TPPAD1-13Y")
      (footprint "eagle-import:P1-13Y")
      (libsource (lib "eagle-import") (part "TPPAD1-13Y"))
    )
    (comp (ref "TP212")
      (value "TPPAD1-13Y")
      (footprint "eagle-import:P1-13Y")
      (libsource (lib "eagle-import") (part "TPPAD1-13Y"))
    )
    (comp (ref "TP213")
      (value "TPPAD1-13Y")
      (footprint "eagle-import:P1-13Y")
      (libsource (lib "eagle-import") (part "TPPAD1-13Y"))
    )
    (comp (ref "TP214")
      (value "TPPAD1-13Y")
      (footprint "eagle-import:P1-13Y")
      (libsource (lib "eagle-import") (part "TPPAD1-13Y"))
    )
    (comp (ref "TP215")
      (value "TPPAD1-13Y")
      (footprint "eagle-import:P1-13Y")
      (libsource (lib "eagle-import") (part "TPPAD1-13Y"))
    )
    (comp (ref "TP216")
      (value "TPPAD1-13Y")
      (footprint "eagle-import:P1-13Y")
      (libsource (lib "eagle-import") (part "TPPAD1-13Y"))
    )
    (comp (ref "TP217")
      (value "TPPAD1-13Y")
      (footprint "eagle-import:P1-13Y")
      (libsource (lib "eagle-import") (part "TPPAD1-13Y"))
    )
    (comp (ref "TP218")
      (value "TPPAD1-13Y")
      (footprint "eagle-import:P1-13Y")
      (libsource (lib "eagle-import") (part "TPPAD1-13Y"))
    )
    (comp (ref "TP219")
      (value "TPPAD1-13Y")
      (footprint "eagle-import:P1-13Y")
      (libsource (lib "eagle-import") (part "TPPAD1-13Y"))
    )
    (comp (ref "TP220")
      (value "TPPAD1-13Y")
      (footprint "eagle-import:P1-13Y")
      (libsource (lib "eagle-import") (part "TPPAD1-13Y"))
    )
    (comp (ref "TP221")
      (value "TPPAD1-13Y")
      (footprint "eagle-import:P1-13Y")
      (libsource (lib "eagle-import") (part "TPPAD1-13Y"))
    )
    (comp (ref "TP222")
      (value "TPPAD1-13Y")
      (footprint "eagle-import:P1-13Y")
      (libsource (lib "eagle-import") (part "TPPAD1-13Y"))
    )
    (comp (ref "TP223")
      (value "TPPAD1-13Y")
      (footprint "eagle-import:P1-13Y")
      (libsource (lib "eagle-import") (part "TPPAD1-13Y"))
    )
    (comp (ref "TP224")
      (value "TPPAD1-13Y")
      (footprint "eagle-import:P1-13Y")
      (libsource (lib "eagle-import") (part "TPPAD1-13Y"))
    )
    (comp (ref "TP225")
      (value "TPPAD1-13Y")
      (footprint "eagle-import:P1-13Y")
      (libsource (lib "eagle-import") (part "TPPAD1-13Y"))
    )
    (comp (ref "TP226")
      (value "TPPAD1-13Y")
      (footprint "eagle-import:P1-13Y")
      (libsource (lib "eagle-import") (part "TPPAD1-13Y"))
    )
    (comp (ref "TP227")
      (value "TPPAD1-13Y")
      (footprint "eagle-import:P1-13Y")
      (libsource (lib "eagle-import") (part "TPPAD1-13Y"))
    )
    (comp (ref "TP228")
      (value "TPPAD1-13Y")
      (footprint "eagle-import:P1-13Y")
      (libsource (lib "eagle-import") (part "TPPAD1-13Y"))
    )
    (comp (ref "TP229")
      (value "TPPAD1-13Y")
      (footprint "eagle-import:P1-13Y")
      (libsource (lib "eagle-import") (part "TPPAD1-13Y"))
    )
    (comp (ref "TP230")
      (value "TPPAD1-13Y")
      (footprint "eagle-import:P1-13Y")
      (libsource (lib "eagle-import") (part "TPPAD1-13Y"))
    )
    (comp (ref "TP231")
      (value "TPPAD1-13Y")
      (footprint "eagle-import:P1-13Y")
      (libsource (lib "eagle-import") (part "TPPAD1-13Y"))
    )
    (comp (ref "TP232")
      (value "TPPAD1-13Y")
      (footprint "eagle-import:P1-13Y")
      (libsource (lib "eagle-import") (part "TPPAD1-13Y"))
    )
    (comp (ref "TP233")
      (value "TPPAD1-13Y")
      (footprint "eagle-import:P1-13Y")
      (libsource (lib "eagle-import") (part "TPPAD1-13Y"))
    )
    (comp (ref "TP234")
      (value "TPPAD1-13Y")
      (footprint "eagle-import:P1-13Y")
      (libsource (lib "eagle-import") (part "TPPAD1-13Y"))
    )
    (comp (ref "TP235")
      (value "TPPAD1-13Y")
      (footprint "eagle-import:P1-13Y")
      (libsource (lib "eagle-import") (part "TPPAD1-13Y"))
    )
    (comp (ref "TP236")
      (value "TPPAD1-13Y")
      (footprint "eagle-import:P1-13Y")
      (libsource (lib "eagle-import") (part "TPPAD1-13Y"))
    )
    (comp (ref "TP237")
      (value "TPPAD1-13Y")
      (footprint "eagle-import:P1-13Y")
      (libsource (lib "eagle-import") (part "TPPAD1-13Y"))
    )
    (comp (ref "TP238")
      (value "TPPAD1-13Y")
      (footprint "eagle-import:P1-13Y")
      (libsource (lib "eagle-import") (part "TPPAD1-13Y"))
    )
    (comp (ref "TP239")
      (value "TPPAD1-13Y")
      (footprint "eagle-import:P1-13Y")
      (libsource (lib "eagle-import") (part "TPPAD1-13Y"))
    )
    (comp (ref "TP240")
      (value "TPPAD1-13Y")
      (footprint "eagle-import:P1-13Y")
      (libsource (lib "eagle-import") (part "TPPAD1-13Y"))
    )
    (comp (ref "TP241")
      (value "TPPAD1-13Y")
      (footprint "eagle-import:P1-13Y")
      (libsource (lib "eagle-import") (part "TPPAD1-13Y"))
    )
    (comp (ref "TP242")
      (value "TPPAD1-13Y")
      (footprint "eagle-import:P1-13Y")
      (libsource (lib "eagle-import") (part "TPPAD1-13Y"))
    )
    (comp (ref "TP243")
      (value "TPPAD1-13Y")
      (footprint "eagle-import:P1-13Y")
      (libsource (lib "eagle-import") (part "TPPAD1-13Y"))
    )
    (comp (ref "TP244")
      (value "TPPAD1-13Y")
      (footprint "eagle-import:P1-13Y")
      (libsource (lib "eagle-import") (part "TPPAD1-13Y"))
    )
    (comp (ref "TP245")
      (value "TPPAD1-13Y")
      (footprint "eagle-import:P1-13Y")
      (libsource (lib "eagle-import") (part "TPPAD1-13Y"))
    )
    (comp (ref "TP246")
      (value "TPPAD1-13Y")
      (footprint "eagle-import:P1-13Y")
      (libsource (lib "eagle-import") (part "TPPAD1-13Y"))
    )
    (comp (ref "TP247")
      (value "TPPAD1-13Y")
      (footprint "eagle-import:P1-13Y")
      (libsource (lib "eagle-import") (part "TPPAD1-13Y"))
    )
    (comp (ref "TP248")
      (value "TPPAD1-13Y")
      (footprint "eagle-import:P1-13Y")
      (libsource (lib "eagle-import") (part "TPPAD1-13Y"))
    )
    (comp (ref "TP249")
      (value "TPPAD1-13Y")
      (footprint "eagle-import:P1-13Y")
      (libsource (lib "eagle-import") (part "TPPAD1-13Y"))
    )
    (comp (ref "TP250")
      (value "TPPAD1-13Y")
      (footprint "eagle-import:P1-13Y")
      (libsource (lib "eagle-import") (part "TPPAD1-13Y"))
    )
    (comp (ref "TP251")
      (value "TPPAD1-13Y")
      (footprint "eagle-import:P1-13Y")
      (libsource (lib "eagle-import") (part "TPPAD1-13Y"))
    )
    (comp (ref "TP252")
      (value "TPPAD1-13Y")
      (footprint "eagle-import:P1-13Y")
      (libsource (lib "eagle-import") (part "TPPAD1-13Y"))
    )
    (comp (ref "TP253")
      (value "TPPAD1-13Y")
      (footprint "eagle-import:P1-13Y")
      (libsource (lib "eagle-import") (part "TPPAD1-13Y"))
    )
    (comp (ref "TP254")
      (value "TPPAD1-13Y")
      (footprint "eagle-import:P1-13Y")
      (libsource (lib "eagle-import") (part "TPPAD1-13Y"))
    )
    (comp (ref "TP255")
      (value "TPPAD1-13Y")
      (footprint "eagle-import:P1-13Y")
      (libsource (lib "eagle-import") (part "TPPAD1-13Y"))
    )
    (comp (ref "TP256")
      (value "TPPAD1-13Y")
      (footprint "eagle-import:P1-13Y")
      (libsource (lib "eagle-import") (part "TPPAD1-13Y"))
    )
    (comp (ref "TP257")
      (value "TPPAD1-13Y")
      (footprint "eagle-import:P1-13Y")
      (libsource (lib "eagle-import") (part "TPPAD1-13Y"))
    )
    (comp (ref "TP258")
      (value "TPPAD1-13Y")
      (footprint "eagle-import:P1-13Y")
      (libsource (lib "eagle-import") (part "TPPAD1-13Y"))
    )
    (comp (ref "TP259")
      (value "TPPAD1-13Y")
      (footprint "eagle-import:P1-13Y")
      (libsource (lib "eagle-import") (part "TPPAD1-13Y"))
    )
    (comp (ref "TP260")
      (value "TPPAD1-13Y")
      (footprint "eagle-import:P1-13Y")
      (libsource (lib "eagle-import") (part "TPPAD1-13Y"))
    )
    (comp (ref "TP261")
      (value "TPPAD1-13Y")
      (footprint "eagle-import:P1-13Y")
      (libsource (lib "eagle-import") (part "TPPAD1-13Y"))
    )
    (comp (ref "TP262")
      (value "TPPAD1-13Y")
      (footprint "eagle-import:P1-13Y")
      (libsource (lib "eagle-import") (part "TPPAD1-13Y"))
    )
    (comp (ref "TP263")
      (value "TPPAD1-13Y")
      (footprint "eagle-import:P1-13Y")
      (libsource (lib "eagle-import") (part "TPPAD1-13Y"))
    )
    (comp (ref "TP264")
      (value "TPPAD1-13Y")
      (footprint "eagle-import:P1-13Y")
      (libsource (lib "eagle-import") (part "TPPAD1-13Y"))
    )
    (comp (ref "TP265")
      (value "TPPAD1-13Y")
      (footprint "eagle-import:P1-13Y")
      (libsource (lib "eagle-import") (part "TPPAD1-13Y"))
    )
    (comp (ref "TP266")
      (value "TPPAD1-13Y")
      (footprint "eagle-import:P1-13Y")
      (libsource (lib "eagle-import") (part "TPPAD1-13Y"))
    )
    (comp (ref "TP267")
      (value "TPPAD1-13Y")
      (footprint "eagle-import:P1-13Y")
      (libsource (lib "eagle-import") (part "TPPAD1-13Y"))
    )
    (comp (ref "TP268")
      (value "TPPAD1-13Y")
      (footprint "eagle-import:P1-13Y")
      (libsource (lib "eagle-import") (part "TPPAD1-13Y"))
    )
    (comp (ref "TP269")
      (value "TPPAD1-13Y")
      (footprint "eagle-import:P1-13Y")
      (libsource (lib "eagle-import") (part "TPPAD1-13Y"))
    )
    (comp (ref "TP270")
      (value "TPPAD1-13Y")
      (footprint "eagle-import:P1-13Y")
      (libsource (lib "eagle-import") (part "TPPAD1-13Y"))
    )
    (comp (ref "TP271")
      (value "TPPAD1-13Y")
      (footprint "eagle-import:P1-13Y")
      (libsource (lib "eagle-import") (part "TPPAD1-13Y"))
    )
    (comp (ref "TP272")
      (value "TPPAD1-13Y")
      (footprint "eagle-import:P1-13Y")
      (libsource (lib "eagle-import") (part "TPPAD1-13Y"))
    )
    (comp (ref "TP273")
      (value "TPPAD1-13Y")
      (footprint "eagle-import:P1-13Y")
      (libsource (lib "eagle-import") (part "TPPAD1-13Y"))
    )
    (comp (ref "TP274")
      (value "TPPAD1-13Y")
      (footprint "eagle-import:P1-13Y")
      (libsource (lib "eagle-import") (part "TPPAD1-13Y"))
    )
    (comp (ref "TP275")
      (value "TPPAD1-13Y")
      (footprint "eagle-import:P1-13Y")
      (libsource (lib "eagle-import") (part "TPPAD1-13Y"))
    )
    (comp (ref "TP276")
      (value "TPPAD1-13Y")
      (footprint "eagle-import:P1-13Y")
      (libsource (lib "eagle-import") (part "TPPAD1-13Y"))
    )
    (comp (ref "TP277")
      (value "TPPAD1-13Y")
      (footprint "eagle-import:P1-13Y")
      (libsource (lib "eagle-import") (part "TPPAD1-13Y"))
    )
    (comp (ref "TP278")
      (value "TPPAD1-13Y")
      (footprint "eagle-import:P1-13Y")
      (libsource (lib "eagle-import") (part "TPPAD1-13Y"))
    )
    (comp (ref "TP279")
      (value "TPPAD1-13Y")
      (footprint "eagle-import:P1-13Y")
      (libsource (lib "eagle-import") (part "TPPAD1-13Y"))
    )
    (comp (ref "TP280")
      (value "TPPAD1-13Y")
      (footprint "eagle-import:P1-13Y")
      (libsource (lib "eagle-import") (part "TPPAD1-13Y"))
    )
    (comp (ref "TP281")
      (value "TPPAD1-13Y")
      (footprint "eagle-import:P1-13Y")
      (libsource (lib "eagle-import") (part "TPPAD1-13Y"))
    )
    (comp (ref "TP282")
      (value "TPPAD1-13Y")
      (footprint "eagle-import:P1-13Y")
      (libsource (lib "eagle-import") (part "TPPAD1-13Y"))
    )
    (comp (ref "TP283")
      (value "TPPAD1-13Y")
      (footprint "eagle-import:P1-13Y")
      (libsource (lib "eagle-import") (part "TPPAD1-13Y"))
    )
    (comp (ref "TP284")
      (value "TPPAD1-13Y")
      (footprint "eagle-import:P1-13Y")
      (libsource (lib "eagle-import") (part "TPPAD1-13Y"))
    )
    (comp (ref "TP285")
      (value "TPPAD1-13Y")
      (footprint "eagle-import:P1-13Y")
      (libsource (lib "eagle-import") (part "TPPAD1-13Y"))
    )
    (comp (ref "TP286")
      (value "TPPAD1-13Y")
      (footprint "eagle-import:P1-13Y")
      (libsource (lib "eagle-import") (part "TPPAD1-13Y"))
    )
    (comp (ref "TP287")
      (value "TPPAD1-13Y")
      (footprint "eagle-import:P1-13Y")
      (libsource (lib "eagle-import") (part "TPPAD1-13Y"))
    )
    (comp (ref "TP288")
      (value "TPPAD1-13Y")
      (footprint "eagle-import:P1-13Y")
      (libsource (lib "eagle-import") (part "TPPAD1-13Y"))
    )
    (comp (ref "TP289")
      (value "TPPAD1-13Y")
      (footprint "eagle-import:P1-13Y")
      (libsource (lib "eagle-import") (part "TPPAD1-13Y"))
    )
    (comp (ref "TP290")
      (value "TPPAD1-13Y")
      (footprint "eagle-import:P1-13Y")
      (libsource (lib "eagle-import") (part "TPPAD1-13Y"))
    )
    (comp (ref "TP291")
      (value "TPPAD1-13Y")
      (footprint "eagle-import:P1-13Y")
      (libsource (lib "eagle-import") (part "TPPAD1-13Y"))
    )
    (comp (ref "TP292")
      (value "TPPAD1-13Y")
      (footprint "eagle-import:P1-13Y")
      (libsource (lib "eagle-import") (part "TPPAD1-13Y"))
    )
    (comp (ref "TP293")
      (value "TPPAD1-13Y")
      (footprint "eagle-import:P1-13Y")
      (libsource (lib "eagle-import") (part "TPPAD1-13Y"))
    )
    (comp (ref "TP294")
      (value "TPPAD1-13Y")
      (footprint "eagle-import:P1-13Y")
      (libsource (lib "eagle-import") (part "TPPAD1-13Y"))
    )
    (comp (ref "TP295")
      (value "TPPAD1-13Y")
      (footprint "eagle-import:P1-13Y")
      (libsource (lib "eagle-import") (part "TPPAD1-13Y"))
    )
    (comp (ref "TP296")
      (value "TPPAD1-13Y")
      (footprint "eagle-import:P1-13Y")
      (libsource (lib "eagle-import") (part "TPPAD1-13Y"))
    )
    (comp (ref "TP297")
      (value "TPPAD1-13Y")
      (footprint "eagle-import:P1-13Y")
      (libsource (lib "eagle-import") (part "TPPAD1-13Y"))
    )
    (comp (ref "TP298")
      (value "TPPAD1-13Y")
      (footprint "eagle-import:P1-13Y")
      (libsource (lib "eagle-import") (part "TPPAD1-13Y"))
    )
    (comp (ref "TP299")
      (value "TPPAD1-13Y")
      (footprint "eagle-import:P1-13Y")
      (libsource (lib "eagle-import") (part "TPPAD1-13Y"))
    )
    (comp (ref "TP300")
      (value "TPPAD1-13Y")
      (footprint "eagle-import:P1-13Y")
      (libsource (lib "eagle-import") (part "TPPAD1-13Y"))
    )
    (comp (ref "TP301")
      (value "TPPAD1-13Y")
      (footprint "eagle-import:P1-13Y")
      (libsource (lib "eagle-import") (part "TPPAD1-13Y"))
    )
    (comp (ref "TP302")
      (value "TPPAD1-13Y")
      (footprint "eagle-import:P1-13Y")
      (libsource (lib "eagle-import") (part "TPPAD1-13Y"))
    )
    (comp (ref "TP303")
      (value "TPPAD1-13Y")
      (footprint "eagle-import:P1-13Y")
      (libsource (lib "eagle-import") (part "TPPAD1-13Y"))
    )
    (comp (ref "TP304")
      (value "TPPAD1-13Y")
      (footprint "eagle-import:P1-13Y")
      (libsource (lib "eagle-import") (part "TPPAD1-13Y"))
    )
    (comp (ref "TP305")
      (value "TPPAD1-13Y")
      (footprint "eagle-import:P1-13Y")
      (libsource (lib "eagle-import") (part "TPPAD1-13Y"))
    )
    (comp (ref "TP306")
      (value "TPPAD1-13Y")
      (footprint "eagle-import:P1-13Y")
      (libsource (lib "eagle-import") (part "TPPAD1-13Y"))
    )
    (comp (ref "TP307")
      (value "TPPAD1-13Y")
      (footprint "eagle-import:P1-13Y")
      (libsource (lib "eagle-import") (part "TPPAD1-13Y"))
    )
    (comp (ref "TP308")
      (value "TPPAD1-13Y")
      (footprint "eagle-import:P1-13Y")
      (libsource (lib "eagle-import") (part "TPPAD1-13Y"))
    )
    (comp (ref "TP309")
      (value "TPPAD1-13Y")
      (footprint "eagle-import:P1-13Y")
      (libsource (lib "eagle-import") (part "TPPAD1-13Y"))
    )
    (comp (ref "TP310")
      (value "TPPAD1-13Y")
      (footprint "eagle-import:P1-13Y")
      (libsource (lib "eagle-import") (part "TPPAD1-13Y"))
    )
    (comp (ref "TP311")
      (value "TPPAD1-13Y")
      (footprint "eagle-import:P1-13Y")
      (libsource (lib "eagle-import") (part "TPPAD1-13Y"))
    )
    (comp (ref "TP312")
      (value "TPPAD1-13Y")
      (footprint "eagle-import:P1-13Y")
      (libsource (lib "eagle-import") (part "TPPAD1-13Y"))
    )
    (comp (ref "TP313")
      (value "TPPAD1-13Y")
      (footprint "eagle-import:P1-13Y")
      (libsource (lib "eagle-import") (part "TPPAD1-13Y"))
    )
    (comp (ref "TP314")
      (value "TPPAD1-13Y")
      (footprint "eagle-import:P1-13Y")
      (libsource (lib "eagle-import") (part "TPPAD1-13Y"))
    )
    (comp (ref "TP315")
      (value "TPPAD1-13Y")
      (footprint "eagle-import:P1-13Y")
      (libsource (lib "eagle-import") (part "TPPAD1-13Y"))
    )
    (comp (ref "TP316")
      (value "TPPAD1-13Y")
      (footprint "eagle-import:P1-13Y")
      (libsource (lib "eagle-import") (part "TPPAD1-13Y"))
    )
    (comp (ref "TP317")
      (value "TPPAD1-13Y")
      (footprint "eagle-import:P1-13Y")
      (libsource (lib "eagle-import") (part "TPPAD1-13Y"))
    )
    (comp (ref "TP318")
      (value "TPPAD1-13Y")
      (footprint "eagle-import:P1-13Y")
      (libsource (lib "eagle-import") (part "TPPAD1-13Y"))
    )
    (comp (ref "TP319")
      (value "TPPAD1-13Y")
      (footprint "eagle-import:P1-13Y")
      (libsource (lib "eagle-import") (part "TPPAD1-13Y"))
    )
    (comp (ref "TP320")
      (value "TPPAD1-13Y")
      (footprint "eagle-import:P1-13Y")
      (libsource (lib "eagle-import") (part "TPPAD1-13Y"))
    )
    (comp (ref "TP321")
      (value "TPPAD1-13Y")
      (footprint "eagle-import:P1-13Y")
      (libsource (lib "eagle-import") (part "TPPAD1-13Y"))
    )
    (comp (ref "TP322")
      (value "TPPAD1-13Y")
      (footprint "eagle-import:P1-13Y")
      (libsource (lib "eagle-import") (part "TPPAD1-13Y"))
    )
    (comp (ref "TP323")
      (value "TPPAD1-13Y")
      (footprint "eagle-import:P1-13Y")
      (libsource (lib "eagle-import") (part "TPPAD1-13Y"))
    )
    (comp (ref "TP324")
      (value "TPPAD1-13Y")
      (footprint "eagle-import:P1-13Y")
      (libsource (lib "eagle-import") (part "TPPAD1-13Y"))
    )
    (comp (ref "TP325")
      (value "TPPAD1-13Y")
      (footprint "eagle-import:P1-13Y")
      (libsource (lib "eagle-import") (part "TPPAD1-13Y"))
    )
    (comp (ref "TP326")
      (value "TPPAD1-13Y")
      (footprint "eagle-import:P1-13Y")
      (libsource (lib "eagle-import") (part "TPPAD1-13Y"))
    )
    (comp (ref "TP327")
      (value "TPPAD1-13Y")
      (footprint "eagle-import:P1-13Y")
      (libsource (lib "eagle-import") (part "TPPAD1-13Y"))
    )
    (comp (ref "TP328")
      (value "TPPAD1-13Y")
      (footprint "eagle-import:P1-13Y")
      (libsource (lib "eagle-import") (part "TPPAD1-13Y"))
    )
    (comp (ref "TP329")
      (value "TPPAD1-13Y")
      (footprint "eagle-import:P1-13Y")
      (libsource (lib "eagle-import") (part "TPPAD1-13Y"))
    )
    (comp (ref "TP330")
      (value "TPPAD1-13Y")
      (footprint "eagle-import:P1-13Y")
      (libsource (lib "eagle-import") (part "TPPAD1-13Y"))
    )
    (comp (ref "TP331")
      (value "TPPAD1-13Y")
      (footprint "eagle-import:P1-13Y")
      (libsource (lib "eagle-import") (part "TPPAD1-13Y"))
    )
    (comp (ref "TP332")
      (value "TPPAD1-13Y")
      (footprint "eagle-import:P1-13Y")
      (libsource (lib "eagle-import") (part "TPPAD1-13Y"))
    )
    (comp (ref "TP333")
      (value "TPPAD1-13Y")
      (footprint "eagle-import:P1-13Y")
      (libsource (lib "eagle-import") (part "TPPAD1-13Y"))
    )
    (comp (ref "TP334")
      (value "TPPAD1-13Y")
      (footprint "eagle-import:P1-13Y")
      (libsource (lib "eagle-import") (part "TPPAD1-13Y"))
    )
    (comp (ref "TP335")
      (value "TPPAD1-13Y")
      (footprint "eagle-import:P1-13Y")
      (libsource (lib "eagle-import") (part "TPPAD1-13Y"))
    )
    (comp (ref "TP336")
      (value "TPPAD1-13Y")
      (footprint "eagle-import:P1-13Y")
      (libsource (lib "eagle-import") (part "TPPAD1-13Y"))
    )
    (comp (ref "TP337")
      (value "TPPAD1-13Y")
      (footprint "eagle-import:P1-13Y")
      (libsource (lib "eagle-import") (part "TPPAD1-13Y"))
    )
    (comp (ref "TP338")
      (value "TPPAD1-13Y")
      (footprint "eagle-import:P1-13Y")
      (libsource (lib "eagle-import") (part "TPPAD1-13Y"))
    )
    (comp (ref "TP339")
      (value "TPPAD1-13Y")
      (footprint "eagle-import:P1-13Y")
      (libsource (lib "eagle-import") (part "TPPAD1-13Y"))
    )
    (comp (ref "TP340")
      (value "TPPAD1-13Y")
      (footprint "eagle-import:P1-13Y")
      (libsource (lib "eagle-import") (part "TPPAD1-13Y"))
    )
    (comp (ref "TP341")
      (value "TPPAD1-13Y")
      (footprint "eagle-import:P1-13Y")
      (libsource (lib "eagle-import") (part "TPPAD1-13Y"))
    )
    (comp (ref "TP342")
      (value "TPPAD1-13Y")
      (footprint "eagle-import:P1-13Y")
      (libsource (lib "eagle-import") (part "TPPAD1-13Y"))
    )
    (comp (ref "TP343")
      (value "TPPAD1-13Y")
      (footprint "eagle-import:P1-13Y")
      (libsource (lib "eagle-import") (part "TPPAD1-13Y"))
    )
    (comp (ref "TP344")
      (value "TPPAD1-13Y")
      (footprint "eagle-import:P1-13Y")
      (libsource (lib "eagle-import") (part "TPPAD1-13Y"))
    )
    (comp (ref "TP345")
      (value "TPPAD1-13Y")
      (footprint "eagle-import:P1-13Y")
      (libsource (lib "eagle-import") (part "TPPAD1-13Y"))
    )
    (comp (ref "TP346")
      (value "TPPAD1-13Y")
      (footprint "eagle-import:P1-13Y")
      (libsource (lib "eagle-import") (part "TPPAD1-13Y"))
    )
    (comp (ref "TP347")
      (value "TPPAD1-13Y")
      (footprint "eagle-import:P1-13Y")
      (libsource (lib "eagle-import") (part "TPPAD1-13Y"))
    )
    (comp (ref "TP348")
      (value "TPPAD1-13Y")
      (footprint "eagle-import:P1-13Y")
      (libsource (lib "eagle-import") (part "TPPAD1-13Y"))
    )
    (comp (ref "TP349")
      (value "TPPAD1-13Y")
      (footprint "eagle-import:P1-13Y")
      (libsource (lib "eagle-import") (part "TPPAD1-13Y"))
    )
    (comp (ref "TP350")
      (value "TPPAD1-13Y")
      (footprint "eagle-import:P1-13Y")
      (libsource (lib "eagle-import") (part "TPPAD1-13Y"))
    )
    (comp (ref "TP351")
      (value "TPPAD1-13Y")
      (footprint "eagle-import:P1-13Y")
      (libsource (lib "eagle-import") (part "TPPAD1-13Y"))
    )
    (comp (ref "TP352")
      (value "TPPAD1-13Y")
      (footprint "eagle-import:P1-13Y")
      (libsource (lib "eagle-import") (part "TPPAD1-13Y"))
    )
    (comp (ref "TP353")
      (value "TPPAD1-13Y")
      (footprint "eagle-import:P1-13Y")
      (libsource (lib "eagle-import") (part "TPPAD1-13Y"))
    )
    (comp (ref "TP354")
      (value "TPPAD1-13Y")
      (footprint "eagle-import:P1-13Y")
      (libsource (lib "eagle-import") (part "TPPAD1-13Y"))
    )
    (comp (ref "TP355")
      (value "TPPAD1-13Y")
      (footprint "eagle-import:P1-13Y")
      (libsource (lib "eagle-import") (part "TPPAD1-13Y"))
    )
    (comp (ref "TP356")
      (value "TPPAD1-13Y")
      (footprint "eagle-import:P1-13Y")
      (libsource (lib "eagle-import") (part "TPPAD1-13Y"))
    )
    (comp (ref "TP357")
      (value "TPPAD1-13Y")
      (footprint "eagle-import:P1-13Y")
      (libsource (lib "eagle-import") (part "TPPAD1-13Y"))
    )
    (comp (ref "TP358")
      (value "TPPAD1-13Y")
      (footprint "eagle-import:P1-13Y")
      (libsource (lib "eagle-import") (part "TPPAD1-13Y"))
    )
    (comp (ref "TP359")
      (value "TPPAD1-13Y")
      (footprint "eagle-import:P1-13Y")
      (libsource (lib "eagle-import") (part "TPPAD1-13Y"))
    )
    (comp (ref "TP360")
      (value "TPPAD1-13Y")
      (footprint "eagle-import:P1-13Y")
      (libsource (lib "eagle-import") (part "TPPAD1-13Y"))
    )
    (comp (ref "TP361")
      (value "TPPAD1-13Y")
      (footprint "eagle-import:P1-13Y")
      (libsource (lib "eagle-import") (part "TPPAD1-13Y"))
    )
    (comp (ref "TP362")
      (value "TPPAD1-13Y")
      (footprint "eagle-import:P1-13Y")
      (libsource (lib "eagle-import") (part "TPPAD1-13Y"))
    )
    (comp (ref "TP363")
      (value "TPPAD1-13Y")
      (footprint "eagle-import:P1-13Y")
      (libsource (lib "eagle-import") (part "TPPAD1-13Y"))
    )
    (comp (ref "TP364")
      (value "TPPAD1-13Y")
      (footprint "eagle-import:P1-13Y")
      (libsource (lib "eagle-import") (part "TPPAD1-13Y"))
    )
    (comp (ref "TP365")
      (value "TPPAD1-13Y")
      (footprint "eagle-import:P1-13Y")
      (libsource (lib "eagle-import") (part "TPPAD1-13Y"))
    )
    (comp (ref "TP366")
      (value "TPPAD1-13Y")
      (footprint "eagle-import:P1-13Y")
      (libsource (lib "eagle-import") (part "TPPAD1-13Y"))
    )
    (comp (ref "TP367")
      (value "TPPAD1-13Y")
      (footprint "eagle-import:P1-13Y")
      (libsource (lib "eagle-import") (part "TPPAD1-13Y"))
    )
    (comp (ref "TP368")
      (value "TPPAD1-13Y")
      (footprint "eagle-import:P1-13Y")
      (libsource (lib "eagle-import") (part "TPPAD1-13Y"))
    )
    (comp (ref "TP369")
      (value "TPPAD1-13Y")
      (footprint "eagle-import:P1-13Y")
      (libsource (lib "eagle-import") (part "TPPAD1-13Y"))
    )
    (comp (ref "TP370")
      (value "TPPAD1-13Y")
      (footprint "eagle-import:P1-13Y")
      (libsource (lib "eagle-import") (part "TPPAD1-13Y"))
    )
    (comp (ref "TP371")
      (value "TPPAD1-13Y")
      (footprint "eagle-import:P1-13Y")
      (libsource (lib "eagle-import") (part "TPPAD1-13Y"))
    )
    (comp (ref "TP372")
      (value "TPPAD1-13Y")
      (footprint "eagle-import:P1-13Y")
      (libsource (lib "eagle-import") (part "TPPAD1-13Y"))
    )
    (comp (ref "TP373")
      (value "TPPAD1-13Y")
      (footprint "eagle-import:P1-13Y")
      (libsource (lib "eagle-import") (part "TPPAD1-13Y"))
    )
    (comp (ref "TP374")
      (value "TPPAD1-13Y")
      (footprint "eagle-import:P1-13Y")
      (libsource (lib "eagle-import") (part "TPPAD1-13Y"))
    )
    (comp (ref "TP375")
      (value "TPPAD1-13Y")
      (footprint "eagle-import:P1-13Y")
      (libsource (lib "eagle-import") (part "TPPAD1-13Y"))
    )
    (comp (ref "TP376")
      (value "TPPAD1-13Y")
      (footprint "eagle-import:P1-13Y")
      (libsource (lib "eagle-import") (part "TPPAD1-13Y"))
    )
    (comp (ref "TP377")
      (value "TPPAD1-13Y")
      (footprint "eagle-import:P1-13Y")
      (libsource (lib "eagle-import") (part "TPPAD1-13Y"))
    )
    (comp (ref "TP378")
      (value "TPPAD1-13Y")
      (footprint "eagle-import:P1-13Y")
      (libsource (lib "eagle-import") (part "TPPAD1-13Y"))
    )
    (comp (ref "TP379")
      (value "TPPAD1-13Y")
      (footprint "eagle-import:P1-13Y")
      (libsource (lib "eagle-import") (part "TPPAD1-13Y"))
    )
    (comp (ref "TP380")
      (value "TPPAD1-13Y")
      (footprint "eagle-import:P1-13Y")
      (libsource (lib "eagle-import") (part "TPPAD1-13Y"))
    )
    (comp (ref "TP381")
      (value "TPPAD1-13Y")
      (footprint "eagle-import:P1-13Y")
      (libsource (lib "eagle-import") (part "TPPAD1-13Y"))
    )
    (comp (ref "TP382")
      (value "TPPAD1-13Y")
      (footprint "eagle-import:P1-13Y")
      (libsource (lib "eagle-import") (part "TPPAD1-13Y"))
    )
    (comp (ref "TP383")
      (value "TPPAD1-13Y")
      (footprint "eagle-import:P1-13Y")
      (libsource (lib "eagle-import") (part "TPPAD1-13Y"))
    )
    (comp (ref "TP384")
      (value "TPPAD1-13Y")
      (footprint "eagle-import:P1-13Y")
      (libsource (lib "eagle-import") (part "TPPAD1-13Y"))
    )
    (comp (ref "TP385")
      (value "TPPAD1-13Y")
      (footprint "eagle-import:P1-13Y")
      (libsource (lib "eagle-import") (part "TPPAD1-13Y"))
    )
    (comp (ref "TP386")
      (value "TPPAD1-13Y")
      (footprint "eagle-import:P1-13Y")
      (libsource (lib "eagle-import") (part "TPPAD1-13Y"))
    )
    (comp (ref "TP387")
      (value "TPPAD1-13Y")
      (footprint "eagle-import:P1-13Y")
      (libsource (lib "eagle-import") (part "TPPAD1-13Y"))
    )
    (comp (ref "TP388")
      (value "TPPAD1-13Y")
      (footprint "eagle-import:P1-13Y")
      (libsource (lib "eagle-import") (part "TPPAD1-13Y"))
    )
    (comp (ref "TP389")
      (value "TPPAD1-13Y")
      (footprint "eagle-import:P1-13Y")
      (libsource (lib "eagle-import") (part "TPPAD1-13Y"))
    )
    (comp (ref "TP390")
      (value "TPPAD1-13Y")
      (footprint "eagle-import:P1-13Y")
      (libsource (lib "eagle-import") (part "TPPAD1-13Y"))
    )
    (comp (ref "TP391")
      (value "TPPAD1-13Y")
      (footprint "eagle-import:P1-13Y")
      (libsource (lib "eagle-import") (part "TPPAD1-13Y"))
    )
    (comp (ref "TP392")
      (value "TPPAD1-13Y")
      (footprint "eagle-import:P1-13Y")
      (libsource (lib "eagle-import") (part "TPPAD1-13Y"))
    )
    (comp (ref "TP393")
      (value "TPPAD1-13Y")
      (footprint "eagle-import:P1-13Y")
      (libsource (lib "eagle-import") (part "TPPAD1-13Y"))
    )
    (comp (ref "TP394")
      (value "TPPAD1-13Y")
      (footprint "eagle-import:P1-13Y")
      (libsource (lib "eagle-import") (part "TPPAD1-13Y"))
    )
    (comp (ref "TP395")
      (value "TPPAD1-13Y")
      (footprint "eagle-import:P1-13Y")
      (libsource (lib "eagle-import") (part "TPPAD1-13Y"))
    )
    (comp (ref "TP396")
      (value "TPPAD1-13Y")
      (footprint "eagle-import:P1-13Y")
      (libsource (lib "eagle-import") (part "TPPAD1-13Y"))
    )
    (comp (ref "TP397")
      (value "TPPAD1-13Y")
      (footprint "eagle-import:P1-13Y")
      (libsource (lib "eagle-import") (part "TPPAD1-13Y"))
    )
    (comp (ref "TP398")
      (value "TPPAD1-13Y")
      (footprint "eagle-import:P1-13Y")
      (libsource (lib "eagle-import") (part "TPPAD1-13Y"))
    )
    (comp (ref "TP399")
      (value "TPPAD1-13Y")
      (footprint "eagle-import:P1-13Y")
      (libsource (lib "eagle-import") (part "TPPAD1-13Y"))
    )
    (comp (ref "TP400")
      (value "TPPAD1-13Y")
      (footprint "eagle-import:P1-13Y")
      (libsource (lib "eagle-import") (part "TPPAD1-13Y"))
    )
    (comp (ref "TP401")
      (value "TPPAD1-13Y")
      (footprint "eagle-import:P1-13Y")
      (libsource (lib "eagle-import") (part "TPPAD1-13Y"))
    )
    (comp (ref "TP402")
      (value "TPPAD1-13Y")
      (footprint "eagle-import:P1-13Y")
      (libsource (lib "eagle-import") (part "TPPAD1-13Y"))
    )
    (comp (ref "TP403")
      (value "TPPAD1-13Y")
      (footprint "eagle-import:P1-13Y")
      (libsource (lib "eagle-import") (part "TPPAD1-13Y"))
    )
    (comp (ref "TP404")
      (value "TPPAD1-13Y")
      (footprint "eagle-import:P1-13Y")
      (libsource (lib "eagle-import") (part "TPPAD1-13Y"))
    )
    (comp (ref "TP405")
      (value "TPPAD1-13Y")
      (footprint "eagle-import:P1-13Y")
      (libsource (lib "eagle-import") (part "TPPAD1-13Y"))
    )
    (comp (ref "TP406")
      (value "TPPAD1-13Y")
      (footprint "eagle-import:P1-13Y")
      (libsource (lib "eagle-import") (part "TPPAD1-13Y"))
    )
    (comp (ref "TP407")
      (value "TPPAD1-13Y")
      (footprint "eagle-import:P1-13Y")
      (libsource (lib "eagle-import") (part "TPPAD1-13Y"))
    )
    (comp (ref "TP408")
      (value "TPPAD1-13Y")
      (footprint "eagle-import:P1-13Y")
      (libsource (lib "eagle-import") (part "TPPAD1-13Y"))
    )
    (comp (ref "TP409")
      (value "TPPAD1-13Y")
      (footprint "eagle-import:P1-13Y")
      (libsource (lib "eagle-import") (part "TPPAD1-13Y"))
    )
    (comp (ref "TP410")
      (value "TPPAD1-13Y")
      (footprint "eagle-import:P1-13Y")
      (libsource (lib "eagle-import") (part "TPPAD1-13Y"))
    )
    (comp (ref "TP411")
      (value "TPPAD1-13Y")
      (footprint "eagle-import:P1-13Y")
      (libsource (lib "eagle-import") (part "TPPAD1-13Y"))
    )
    (comp (ref "TP412")
      (value "TPPAD1-13Y")
      (footprint "eagle-import:P1-13Y")
      (libsource (lib "eagle-import") (part "TPPAD1-13Y"))
    )
    (comp (ref "TP413")
      (value "TPPAD1-13Y")
      (footprint "eagle-import:P1-13Y")
      (libsource (lib "eagle-import") (part "TPPAD1-13Y"))
    )
    (comp (ref "TP414")
      (value "TPPAD1-13Y")
      (footprint "eagle-import:P1-13Y")
      (libsource (lib "eagle-import") (part "TPPAD1-13Y"))
    )
    (comp (ref "TP415")
      (value "TPPAD1-13Y")
      (footprint "eagle-import:P1-13Y")
      (libsource (lib "eagle-import") (part "TPPAD1-13Y"))
    )
    (comp (ref "TP416")
      (value "TPPAD1-13Y")
      (footprint "eagle-import:P1-13Y")
      (libsource (lib "eagle-import") (part "TPPAD1-13Y"))
    )
    (comp (ref "TP417")
      (value "TPPAD1-13Y")
      (footprint "eagle-import:P1-13Y")
      (libsource (lib "eagle-import") (part "TPPAD1-13Y"))
    )
    (comp (ref "TP418")
      (value "TPPAD1-13Y")
      (footprint "eagle-import:P1-13Y")
      (libsource (lib "eagle-import") (part "TPPAD1-13Y"))
    )
    (comp (ref "TP419")
      (value "TPPAD1-13Y")
      (footprint "eagle-import:P1-13Y")
      (libsource (lib "eagle-import") (part "TPPAD1-13Y"))
    )
    (comp (ref "TP420")
      (value "TPPAD1-13Y")
      (footprint "eagle-import:P1-13Y")
      (libsource (lib "eagle-import") (part "TPPAD1-13Y"))
    )
    (comp (ref "TP421")
      (value "TPPAD1-13Y")
      (footprint "eagle-import:P1-13Y")
      (libsource (lib "eagle-import") (part "TPPAD1-13Y"))
    )
    (comp (ref "TP422")
      (value "TPPAD1-13Y")
      (footprint "eagle-import:P1-13Y")
      (libsource (lib "eagle-import") (part "TPPAD1-13Y"))
    )
    (comp (ref "TP423")
      (value "TPPAD1-13Y")
      (footprint "eagle-import:P1-13Y")
      (libsource (lib "eagle-import") (part "TPPAD1-13Y"))
    )
    (comp (ref "TP424")
      (value "TPPAD1-13Y")
      (footprint "eagle-import:P1-13Y")
      (libsource (lib "eagle-import") (part "TPPAD1-13Y"))
    )
    (comp (ref "TP425")
      (value "TPPAD1-13Y")
      (footprint "eagle-import:P1-13Y")
      (libsource (lib "eagle-import") (part "TPPAD1-13Y"))
    )
    (comp (ref "TP426")
      (value "TPPAD1-13Y")
      (footprint "eagle-import:P1-13Y")
      (libsource (lib "eagle-import") (part "TPPAD1-13Y"))
    )
    (comp (ref "TP427")
      (value "TPPAD1-13Y")
      (footprint "eagle-import:P1-13Y")
      (libsource (lib "eagle-import") (part "TPPAD1-13Y"))
    )
    (comp (ref "TP428")
      (value "TPPAD1-13Y")
      (footprint "eagle-import:P1-13Y")
      (libsource (lib "eagle-import") (part "TPPAD1-13Y"))
    )
    (comp (ref "TP429")
      (value "TPPAD1-13Y")
      (footprint "eagle-import:P1-13Y")
      (libsource (lib "eagle-import") (part "TPPAD1-13Y"))
    )
    (comp (ref "TP430")
      (value "TPPAD1-13Y")
      (footprint "eagle-import:P1-13Y")
      (libsource (lib "eagle-import") (part "TPPAD1-13Y"))
    )
    (comp (ref "TP431")
      (value "TPPAD1-13Y")
      (footprint "eagle-import:P1-13Y")
      (libsource (lib "eagle-import") (part "TPPAD1-13Y"))
    )
    (comp (ref "TP432")
      (value "TPPAD1-13Y")
      (footprint "eagle-import:P1-13Y")
      (libsource (lib "eagle-import") (part "TPPAD1-13Y"))
    )
    (comp (ref "TP433")
      (value "TPPAD1-13Y")
      (footprint "eagle-import:P1-13Y")
      (libsource (lib "eagle-import") (part "TPPAD1-13Y"))
    )
    (comp (ref "TP434")
      (value "TPPAD1-13Y")
      (footprint "eagle-import:P1-13Y")
      (libsource (lib "eagle-import") (part "TPPAD1-13Y"))
    )
    (comp (ref "TP435")
      (value "TPPAD1-13Y")
      (footprint "eagle-import:P1-13Y")
      (libsource (lib "eagle-import") (part "TPPAD1-13Y"))
    )
    (comp (ref "TP436")
      (value "TPPAD1-13Y")
      (footprint "eagle-import:P1-13Y")
      (libsource (lib "eagle-import") (part "TPPAD1-13Y"))
    )
    (comp (ref "TP437")
      (value "TPPAD1-13Y")
      (footprint "eagle-import:P1-13Y")
      (libsource (lib "eagle-import") (part "TPPAD1-13Y"))
    )
    (comp (ref "TP438")
      (value "TPPAD1-13Y")
      (footprint "eagle-import:P1-13Y")
      (libsource (lib "eagle-import") (part "TPPAD1-13Y"))
    )
    (comp (ref "TP439")
      (value "TPPAD1-13Y")
      (footprint "eagle-import:P1-13Y")
      (libsource (lib "eagle-import") (part "TPPAD1-13Y"))
    )
    (comp (ref "TP440")
      (value "TPPAD1-13Y")
      (footprint "eagle-import:P1-13Y")
      (libsource (lib "eagle-import") (part "TPPAD1-13Y"))
    )
    (comp (ref "TP441")
      (value "TPPAD1-13Y")
      (footprint "eagle-import:P1-13Y")
      (libsource (lib "eagle-import") (part "TPPAD1-13Y"))
    )
    (comp (ref "TP442")
      (value "TPPAD1-13Y")
      (footprint "eagle-import:P1-13Y")
      (libsource (lib "eagle-import") (part "TPPAD1-13Y"))
    )
    (comp (ref "TP443")
      (value "TPPAD1-13Y")
      (footprint "eagle-import:P1-13Y")
      (libsource (lib "eagle-import") (part "TPPAD1-13Y"))
    )
    (comp (ref "TP444")
      (value "TPPAD1-13Y")
      (footprint "eagle-import:P1-13Y")
      (libsource (lib "eagle-import") (part "TPPAD1-13Y"))
    )
    (comp (ref "TP445")
      (value "TPPAD1-13Y")
      (footprint "eagle-import:P1-13Y")
      (libsource (lib "eagle-import") (part "TPPAD1-13Y"))
    )
    (comp (ref "TP446")
      (value "TPPAD1-13Y")
      (footprint "eagle-import:P1-13Y")
      (libsource (lib "eagle-import") (part "TPPAD1-13Y"))
    )
    (comp (ref "TP447")
      (value "TPPAD1-13Y")
      (footprint "eagle-import:P1-13Y")
      (libsource (lib "eagle-import") (part "TPPAD1-13Y"))
    )
    (comp (ref "TP448")
      (value "TPPAD1-13Y")
      (footprint "eagle-import:P1-13Y")
      (libsource (lib "eagle-import") (part "TPPAD1-13Y"))
    )
    (comp (ref "TP449")
      (value "TPPAD1-13Y")
      (footprint "eagle-import:P1-13Y")
      (libsource (lib "eagle-import") (part "TPPAD1-13Y"))
    )
    (comp (ref "TP450")
      (value "TPPAD1-13Y")
      (footprint "eagle-import:P1-13Y")
      (libsource (lib "eagle-import") (part "TPPAD1-13Y"))
    )
    (comp (ref "TP451")
      (value "TPPAD1-13Y")
      (footprint "eagle-import:P1-13Y")
      (libsource (lib "eagle-import") (part "TPPAD1-13Y"))
    )
    (comp (ref "TP452")
      (value "TPPAD1-13Y")
      (footprint "eagle-import:P1-13Y")
      (libsource (lib "eagle-import") (part "TPPAD1-13Y"))
    )
    (comp (ref "TP453")
      (value "TPPAD1-13Y")
      (footprint "eagle-import:P1-13Y")
      (libsource (lib "eagle-import") (part "TPPAD1-13Y"))
    )
    (comp (ref "TP454")
      (value "TPPAD1-13Y")
      (footprint "eagle-import:P1-13Y")
      (libsource (lib "eagle-import") (part "TPPAD1-13Y"))
    )
    (comp (ref "TP455")
      (value "TPPAD1-13Y")
      (footprint "eagle-import:P1-13Y")
      (libsource (lib "eagle-import") (part "TPPAD1-13Y"))
    )
    (comp (ref "TP456")
      (value "TPPAD1-13Y")
      (footprint "eagle-import:P1-13Y")
      (libsource (lib "eagle-import") (part "TPPAD1-13Y"))
    )
    (comp (ref "TP457")
      (value "TPPAD1-13Y")
      (footprint "eagle-import:P1-13Y")
      (libsource (lib "eagle-import") (part "TPPAD1-13Y"))
    )
    (comp (ref "TP458")
      (value "TPPAD1-13Y")
      (footprint "eagle-import:P1-13Y")
      (libsource (lib "eagle-import") (part "TPPAD1-13Y"))
    )
    (comp (ref "TP459")
      (value "TPPAD1-13Y")
      (footprint "eagle-import:P1-13Y")
      (libsource (lib "eagle-import") (part "TPPAD1-13Y"))
    )
    (comp (ref "TP460")
      (value "TPPAD1-13Y")
      (footprint "eagle-import:P1-13Y")
      (libsource (lib "eagle-import") (part "TPPAD1-13Y"))
    )
    (comp (ref "TP461")
      (value "TPPAD1-13Y")
      (footprint "eagle-import:P1-13Y")
      (libsource (lib "eagle-import") (part "TPPAD1-13Y"))
    )
    (comp (ref "TP462")
      (value "TPPAD1-13Y")
      (footprint "eagle-import:P1-13Y")
      (libsource (lib "eagle-import") (part "TPPAD1-13Y"))
    )
    (comp (ref "TP463")
      (value "TPPAD1-13Y")
      (footprint "eagle-import:P1-13Y")
      (libsource (lib "eagle-import") (part "TPPAD1-13Y"))
    )
    (comp (ref "TP464")
      (value "TPPAD1-13Y")
      (footprint "eagle-import:P1-13Y")
      (libsource (lib "eagle-import") (part "TPPAD1-13Y"))
    )
    (comp (ref "TP465")
      (value "TPPAD1-13Y")
      (footprint "eagle-import:P1-13Y")
      (libsource (lib "eagle-import") (part "TPPAD1-13Y"))
    )
    (comp (ref "TP466")
      (value "TPPAD1-13Y")
      (footprint "eagle-import:P1-13Y")
      (libsource (lib "eagle-import") (part "TPPAD1-13Y"))
    )
    (comp (ref "TP467")
      (value "TPPAD1-13Y")
      (footprint "eagle-import:P1-13Y")
      (libsource (lib "eagle-import") (part "TPPAD1-13Y"))
    )
    (comp (ref "TP468")
      (value "TPPAD1-13Y")
      (footprint "eagle-import:P1-13Y")
      (libsource (lib "eagle-import") (part "TPPAD1-13Y"))
    )
    (comp (ref "TP469")
      (value "TPPAD1-13Y")
      (footprint "eagle-import:P1-13Y")
      (libsource (lib "eagle-import") (part "TPPAD1-13Y"))
    )
    (comp (ref "TP470")
      (value "TPPAD1-13Y")
      (footprint "eagle-import:P1-13Y")
      (libsource (lib "eagle-import") (part "TPPAD1-13Y"))
    )
    (comp (ref "TP471")
      (value "TPPAD1-13Y")
      (footprint "eagle-import:P1-13Y")
      (libsource (lib "eagle-import") (part "TPPAD1-13Y"))
    )
    (comp (ref "TP472")
      (value "TPPAD1-13Y")
      (footprint "eagle-import:P1-13Y")
      (libsource (lib "eagle-import") (part "TPPAD1-13Y"))
    )
    (comp (ref "TP473")
      (value "TPPAD1-13Y")
      (footprint "eagle-import:P1-13Y")
      (libsource (lib "eagle-import") (part "TPPAD1-13Y"))
    )
    (comp (ref "U$1")
      (value "SINGLE")
      (footprint "eagle-import:EDGE-CON2")
      (libsource (lib "eagle-import") (part "SINGLE"))
    )
    (comp (ref "U$3")
      (value "OUTLINE-SINGLE")
      (footprint "eagle-import:SINGLE")
      (libsource (lib "eagle-import") (part "OUTLINE-SINGLE"))
    )
    (comp (ref "U$5")
      (value "THRU-HOLE2C")
      (footprint "eagle-import:THRU-HOLEC")
      (libsource (lib "eagle-import") (part "THRU-HOLE2C"))
    )
  )
  (nets
    (net (code "1") (name "Net-(TP1-PadTP)") (class "Default")
      (node (ref "TP1") (pin "TP") (pinfunction "TP_TP") (pintype "input"))
      (node (ref "TP2") (pin "TP") (pinfunction "TP_TP") (pintype "input"))
    )
    (net (code "2") (name "Net-(TP3-PadTP)") (class "Default")
      (node (ref "TP3") (pin "TP") (pinfunction "TP_TP") (pintype "input"))
      (node (ref "TP4") (pin "TP") (pinfunction "TP_TP") (pintype "input"))
      (node (ref "TP5") (pin "TP") (pinfunction "TP_TP") (pintype "input"))
      (node (ref "TP6") (pin "TP") (pinfunction "TP_TP") (pintype "input"))
    )
    (net (code "3") (name "Net-(TP7-PadTP)") (class "Default")
      (node (ref "TP7") (pin "TP") (pinfunction "TP_TP") (pintype "input"))
      (node (ref "TP8") (pin "TP") (pinfunction "TP_TP") (pintype "input"))
      (node (ref "TP9") (pin "TP") (pinfunction "TP_TP") (pintype "input"))
    )
    (net (code "4") (name "Net-(TP10-PadTP)") (class "Default")
      (node (ref "TP10") (pin "TP") (pinfunction "TP_TP") (pintype "input"))
      (node (ref "TP11") (pin "TP") (pinfunction "TP_TP") (pintype "input"))
      (node (ref "TP12") (pin "TP") (pinfunction "TP_TP") (pintype "input"))
      (node (ref "TP13") (pin "TP") (pinfunction "TP_TP") (pintype "input"))
    )
    (net (code "5") (name "Net-(TP14-PadTP)") (class "Default")
      (node (ref "TP14") (pin "TP") (pinfunction "TP_TP") (pintype "input"))
      (node (ref "TP15") (pin "TP") (pinfunction "TP_TP") (pintype "input"))
      (node (ref "TP16") (pin "TP") (pinfunction "TP_TP") (pintype "input"))
    )
    (net (code "6") (name "Net-(TP17-PadTP)") (class "Default")
      (node (ref "TP17") (pin "TP") (pinfunction "TP_TP") (pintype "input"))
      (node (ref "TP18") (pin "TP") (pinfunction "TP_TP") (pintype "input"))
      (node (ref "TP19") (pin "TP") (pinfunction "TP_TP") (pintype "input"))
      (node (ref "TP20") (pin "TP") (pinfunction "TP_TP") (pintype "input"))
    )
    (net (code "7") (name "Net-(TP21-PadTP)") (class "Default")
      (node (ref "TP21") (pin "TP") (pinfunction "TP_TP") (pintype "input"))
      (node (ref "TP22") (pin "TP") (pinfunction "TP_TP") (pintype "input"))
      (node (ref "TP23") (pin "TP") (pinfunction "TP_TP") (pintype "input"))
      (node (ref "TP24") (pin "TP") (pinfunction "TP_TP") (pintype "input"))
    )
    (net (code "8") (name "Net-(TP25-PadTP)") (class "Default")
      (node (ref "TP25") (pin "TP") (pinfunction "TP_TP") (pintype "input"))
      (node (ref "TP26") (pin "TP") (pinfunction "TP_TP") (pintype "input"))
      (node (ref "TP27") (pin "TP") (pinfunction "TP_TP") (pintype "input"))
      (node (ref "TP28") (pin "TP") (pinfunction "TP_TP") (pintype "input"))
    )
    (net (code "9") (name "Net-(TP29-PadTP)") (class "Default")
      (node (ref "TP29") (pin "TP") (pinfunction "TP_TP") (pintype "input"))
      (node (ref "TP30") (pin "TP") (pinfunction "TP_TP") (pintype "input"))
      (node (ref "TP31") (pin "TP") (pinfunction "TP_TP") (pintype "input"))
      (node (ref "TP32") (pin "TP") (pinfunction "TP_TP") (pintype "input"))
    )
    (net (code "10") (name "Net-(TP33-PadTP)") (class "Default")
      (node (ref "TP33") (pin "TP") (pinfunction "TP_TP") (pintype "input"))
      (node (ref "TP34") (pin "TP") (pinfunction "TP_TP") (pintype "input"))
      (node (ref "TP35") (pin "TP") (pinfunction "TP_TP") (pintype "input"))
      (node (ref "TP36") (pin "TP") (pinfunction "TP_TP") (pintype "input"))
    )
    (net (code "11") (name "Net-(TP37-PadTP)") (class "Default")
      (node (ref "TP37") (pin "TP") (pinfunction "TP_TP") (pintype "input"))
      (node (ref "TP38") (pin "TP") (pinfunction "TP_TP") (pintype "input"))
      (node (ref "TP39") (pin "TP") (pinfunction "TP_TP") (pintype "input"))
      (node (ref "TP40") (pin "TP") (pinfunction "TP_TP") (pintype "input"))
    )
    (net (code "12") (name "Net-(TP41-PadTP)") (class "Default")
      (node (ref "TP41") (pin "TP") (pinfunction "TP_TP") (pintype "input"))
      (node (ref "TP42") (pin "TP") (pinfunction "TP_TP") (pintype "input"))
      (node (ref "TP43") (pin "TP") (pinfunction "TP_TP") (pintype "input"))
      (node (ref "TP44") (pin "TP") (pinfunction "TP_TP") (pintype "input"))
    )
    (net (code "13") (name "Net-(TP45-PadTP)") (class "Default")
      (node (ref "TP45") (pin "TP") (pinfunction "TP_TP") (pintype "input"))
      (node (ref "TP46") (pin "TP") (pinfunction "TP_TP") (pintype "input"))
      (node (ref "TP47") (pin "TP") (pinfunction "TP_TP") (pintype "input"))
      (node (ref "TP48") (pin "TP") (pinfunction "TP_TP") (pintype "input"))
    )
    (net (code "14") (name "Net-(TP49-PadTP)") (class "Default")
      (node (ref "TP49") (pin "TP") (pinfunction "TP_TP") (pintype "input"))
      (node (ref "TP50") (pin "TP") (pinfunction "TP_TP") (pintype "input"))
      (node (ref "TP51") (pin "TP") (pinfunction "TP_TP") (pintype "input"))
      (node (ref "TP52") (pin "TP") (pinfunction "TP_TP") (pintype "input"))
    )
    (net (code "15") (name "Net-(TP53-PadTP)") (class "Default")
      (node (ref "TP53") (pin "TP") (pinfunction "TP_TP") (pintype "input"))
      (node (ref "TP54") (pin "TP") (pinfunction "TP_TP") (pintype "input"))
      (node (ref "TP55") (pin "TP") (pinfunction "TP_TP") (pintype "input"))
      (node (ref "TP56") (pin "TP") (pinfunction "TP_TP") (pintype "input"))
    )
    (net (code "16") (name "Net-(TP57-PadTP)") (class "Default")
      (node (ref "TP57") (pin "TP") (pinfunction "TP_TP") (pintype "input"))
      (node (ref "TP58") (pin "TP") (pinfunction "TP_TP") (pintype "input"))
      (node (ref "TP59") (pin "TP") (pinfunction "TP_TP") (pintype "input"))
      (node (ref "TP60") (pin "TP") (pinfunction "TP_TP") (pintype "input"))
    )
    (net (code "17") (name "Net-(TP61-PadTP)") (class "Default")
      (node (ref "TP61") (pin "TP") (pinfunction "TP_TP") (pintype "input"))
      (node (ref "TP62") (pin "TP") (pinfunction "TP_TP") (pintype "input"))
      (node (ref "TP63") (pin "TP") (pinfunction "TP_TP") (pintype "input"))
      (node (ref "TP64") (pin "TP") (pinfunction "TP_TP") (pintype "input"))
    )
    (net (code "18") (name "Net-(TP65-PadTP)") (class "Default")
      (node (ref "TP65") (pin "TP") (pinfunction "TP_TP") (pintype "input"))
      (node (ref "TP66") (pin "TP") (pinfunction "TP_TP") (pintype "input"))
      (node (ref "TP67") (pin "TP") (pinfunction "TP_TP") (pintype "input"))
      (node (ref "TP68") (pin "TP") (pinfunction "TP_TP") (pintype "input"))
    )
    (net (code "19") (name "Net-(TP69-PadTP)") (class "Default")
      (node (ref "TP69") (pin "TP") (pinfunction "TP_TP") (pintype "input"))
      (node (ref "TP70") (pin "TP") (pinfunction "TP_TP") (pintype "input"))
      (node (ref "TP71") (pin "TP") (pinfunction "TP_TP") (pintype "input"))
      (node (ref "TP72") (pin "TP") (pinfunction "TP_TP") (pintype "input"))
    )
    (net (code "20") (name "Net-(TP73-PadTP)") (class "Default")
      (node (ref "TP73") (pin "TP") (pinfunction "TP_TP") (pintype "input"))
      (node (ref "TP74") (pin "TP") (pinfunction "TP_TP") (pintype "input"))
      (node (ref "TP75") (pin "TP") (pinfunction "TP_TP") (pintype "input"))
      (node (ref "TP76") (pin "TP") (pinfunction "TP_TP") (pintype "input"))
    )
    (net (code "21") (name "Net-(TP77-PadTP)") (class "Default")
      (node (ref "TP77") (pin "TP") (pinfunction "TP_TP") (pintype "input"))
      (node (ref "TP78") (pin "TP") (pinfunction "TP_TP") (pintype "input"))
      (node (ref "TP79") (pin "TP") (pinfunction "TP_TP") (pintype "input"))
      (node (ref "TP80") (pin "TP") (pinfunction "TP_TP") (pintype "input"))
    )
    (net (code "22") (name "Net-(TP81-PadTP)") (class "Default")
      (node (ref "TP81") (pin "TP") (pinfunction "TP_TP") (pintype "input"))
      (node (ref "TP82") (pin "TP") (pinfunction "TP_TP") (pintype "input"))
      (node (ref "TP83") (pin "TP") (pinfunction "TP_TP") (pintype "input"))
      (node (ref "TP84") (pin "TP") (pinfunction "TP_TP") (pintype "input"))
    )
    (net (code "23") (name "Net-(TP85-PadTP)") (class "Default")
      (node (ref "TP85") (pin "TP") (pinfunction "TP_TP") (pintype "input"))
      (node (ref "TP86") (pin "TP") (pinfunction "TP_TP") (pintype "input"))
      (node (ref "TP87") (pin "TP") (pinfunction "TP_TP") (pintype "input"))
      (node (ref "TP88") (pin "TP") (pinfunction "TP_TP") (pintype "input"))
    )
    (net (code "24") (name "Net-(TP89-PadTP)") (class "Default")
      (node (ref "TP89") (pin "TP") (pinfunction "TP_TP") (pintype "input"))
      (node (ref "TP90") (pin "TP") (pinfunction "TP_TP") (pintype "input"))
      (node (ref "TP91") (pin "TP") (pinfunction "TP_TP") (pintype "input"))
      (node (ref "TP92") (pin "TP") (pinfunction "TP_TP") (pintype "input"))
    )
    (net (code "25") (name "Net-(TP93-PadTP)") (class "Default")
      (node (ref "TP93") (pin "TP") (pinfunction "TP_TP") (pintype "input"))
      (node (ref "TP94") (pin "TP") (pinfunction "TP_TP") (pintype "input"))
      (node (ref "TP95") (pin "TP") (pinfunction "TP_TP") (pintype "input"))
      (node (ref "TP96") (pin "TP") (pinfunction "TP_TP") (pintype "input"))
    )
    (net (code "26") (name "Net-(TP100-PadTP)") (class "Default")
      (node (ref "TP100") (pin "TP") (pinfunction "TP_TP") (pintype "input"))
      (node (ref "TP97") (pin "TP") (pinfunction "TP_TP") (pintype "input"))
      (node (ref "TP98") (pin "TP") (pinfunction "TP_TP") (pintype "input"))
      (node (ref "TP99") (pin "TP") (pinfunction "TP_TP") (pintype "input"))
    )
    (net (code "27") (name "Net-(TP101-PadTP)") (class "Default")
      (node (ref "TP101") (pin "TP") (pinfunction "TP_TP") (pintype "input"))
      (node (ref "TP102") (pin "TP") (pinfunction "TP_TP") (pintype "input"))
      (node (ref "TP103") (pin "TP") (pinfunction "TP_TP") (pintype "input"))
      (node (ref "TP104") (pin "TP") (pinfunction "TP_TP") (pintype "input"))
    )
    (net (code "28") (name "Net-(TP105-PadTP)") (class "Default")
      (node (ref "TP105") (pin "TP") (pinfunction "TP_TP") (pintype "input"))
      (node (ref "TP106") (pin "TP") (pinfunction "TP_TP") (pintype "input"))
      (node (ref "TP107") (pin "TP") (pinfunction "TP_TP") (pintype "input"))
      (node (ref "TP108") (pin "TP") (pinfunction "TP_TP") (pintype "input"))
    )
    (net (code "29") (name "Net-(TP109-PadTP)") (class "Default")
      (node (ref "TP109") (pin "TP") (pinfunction "TP_TP") (pintype "input"))
      (node (ref "TP110") (pin "TP") (pinfunction "TP_TP") (pintype "input"))
      (node (ref "TP111") (pin "TP") (pinfunction "TP_TP") (pintype "input"))
      (node (ref "TP112") (pin "TP") (pinfunction "TP_TP") (pintype "input"))
    )
    (net (code "30") (name "Net-(TP113-PadTP)") (class "Default")
      (node (ref "TP113") (pin "TP") (pinfunction "TP_TP") (pintype "input"))
      (node (ref "TP114") (pin "TP") (pinfunction "TP_TP") (pintype "input"))
      (node (ref "TP115") (pin "TP") (pinfunction "TP_TP") (pintype "input"))
      (node (ref "TP116") (pin "TP") (pinfunction "TP_TP") (pintype "input"))
    )
    (net (code "31") (name "Net-(TP117-PadTP)") (class "Default")
      (node (ref "TP117") (pin "TP") (pinfunction "TP_TP") (pintype "input"))
      (node (ref "TP118") (pin "TP") (pinfunction "TP_TP") (pintype "input"))
      (node (ref "TP119") (pin "TP") (pinfunction "TP_TP") (pintype "input"))
      (node (ref "TP120") (pin "TP") (pinfunction "TP_TP") (pintype "input"))
    )
    (net (code "32") (name "Net-(TP121-PadTP)") (class "Default")
      (node (ref "TP121") (pin "TP") (pinfunction "TP_TP") (pintype "input"))
      (node (ref "TP122") (pin "TP") (pinfunction "TP_TP") (pintype "input"))
      (node (ref "TP123") (pin "TP") (pinfunction "TP_TP") (pintype "input"))
      (node (ref "TP124") (pin "TP") (pinfunction "TP_TP") (pintype "input"))
    )
    (net (code "33") (name "Net-(TP125-PadTP)") (class "Default")
      (node (ref "TP125") (pin "TP") (pinfunction "TP_TP") (pintype "input"))
      (node (ref "TP126") (pin "TP") (pinfunction "TP_TP") (pintype "input"))
      (node (ref "TP127") (pin "TP") (pinfunction "TP_TP") (pintype "input"))
      (node (ref "TP128") (pin "TP") (pinfunction "TP_TP") (pintype "input"))
    )
    (net (code "34") (name "Net-(TP129-PadTP)") (class "Default")
      (node (ref "TP129") (pin "TP") (pinfunction "TP_TP") (pintype "input"))
      (node (ref "TP130") (pin "TP") (pinfunction "TP_TP") (pintype "input"))
      (node (ref "TP131") (pin "TP") (pinfunction "TP_TP") (pintype "input"))
      (node (ref "TP132") (pin "TP") (pinfunction "TP_TP") (pintype "input"))
    )
    (net (code "35") (name "Net-(TP133-PadTP)") (class "Default")
      (node (ref "TP133") (pin "TP") (pinfunction "TP_TP") (pintype "input"))
      (node (ref "TP134") (pin "TP") (pinfunction "TP_TP") (pintype "input"))
      (node (ref "TP135") (pin "TP") (pinfunction "TP_TP") (pintype "input"))
      (node (ref "TP136") (pin "TP") (pinfunction "TP_TP") (pintype "input"))
    )
    (net (code "36") (name "Net-(TP137-PadTP)") (class "Default")
      (node (ref "TP137") (pin "TP") (pinfunction "TP_TP") (pintype "input"))
      (node (ref "TP138") (pin "TP") (pinfunction "TP_TP") (pintype "input"))
      (node (ref "TP139") (pin "TP") (pinfunction "TP_TP") (pintype "input"))
      (node (ref "TP140") (pin "TP") (pinfunction "TP_TP") (pintype "input"))
    )
    (net (code "37") (name "Net-(TP141-PadTP)") (class "Default")
      (node (ref "TP141") (pin "TP") (pinfunction "TP_TP") (pintype "input"))
      (node (ref "TP142") (pin "TP") (pinfunction "TP_TP") (pintype "input"))
      (node (ref "TP143") (pin "TP") (pinfunction "TP_TP") (pintype "input"))
      (node (ref "TP144") (pin "TP") (pinfunction "TP_TP") (pintype "input"))
    )
    (net (code "38") (name "Net-(TP145-PadTP)") (class "Default")
      (node (ref "TP145") (pin "TP") (pinfunction "TP_TP") (pintype "input"))
      (node (ref "TP146") (pin "TP") (pinfunction "TP_TP") (pintype "input"))
      (node (ref "TP147") (pin "TP") (pinfunction "TP_TP") (pintype "input"))
      (node (ref "TP148") (pin "TP") (pinfunction "TP_TP") (pintype "input"))
    )
    (net (code "39") (name "Net-(TP149-PadTP)") (class "Default")
      (node (ref "TP149") (pin "TP") (pinfunction "TP_TP") (pintype "input"))
      (node (ref "TP150") (pin "TP") (pinfunction "TP_TP") (pintype "input"))
      (node (ref "TP151") (pin "TP") (pinfunction "TP_TP") (pintype "input"))
      (node (ref "TP152") (pin "TP") (pinfunction "TP_TP") (pintype "input"))
    )
    (net (code "40") (name "Net-(TP153-PadTP)") (class "Default")
      (node (ref "TP153") (pin "TP") (pinfunction "TP_TP") (pintype "input"))
      (node (ref "TP154") (pin "TP") (pinfunction "TP_TP") (pintype "input"))
      (node (ref "TP155") (pin "TP") (pinfunction "TP_TP") (pintype "input"))
      (node (ref "TP156") (pin "TP") (pinfunction "TP_TP") (pintype "input"))
    )
    (net (code "41") (name "Net-(TP157-PadTP)") (class "Default")
      (node (ref "TP157") (pin "TP") (pinfunction "TP_TP") (pintype "input"))
      (node (ref "TP158") (pin "TP") (pinfunction "TP_TP") (pintype "input"))
      (node (ref "TP159") (pin "TP") (pinfunction "TP_TP") (pintype "input"))
      (node (ref "TP160") (pin "TP") (pinfunction "TP_TP") (pintype "input"))
    )
    (net (code "42") (name "Net-(TP161-PadTP)") (class "Default")
      (node (ref "TP161") (pin "TP") (pinfunction "TP_TP") (pintype "input"))
      (node (ref "TP162") (pin "TP") (pinfunction "TP_TP") (pintype "input"))
      (node (ref "TP163") (pin "TP") (pinfunction "TP_TP") (pintype "input"))
      (node (ref "TP164") (pin "TP") (pinfunction "TP_TP") (pintype "input"))
    )
    (net (code "43") (name "Net-(TP165-PadTP)") (class "Default")
      (node (ref "TP165") (pin "TP") (pinfunction "TP_TP") (pintype "input"))
      (node (ref "TP166") (pin "TP") (pinfunction "TP_TP") (pintype "input"))
      (node (ref "TP167") (pin "TP") (pinfunction "TP_TP") (pintype "input"))
      (node (ref "TP168") (pin "TP") (pinfunction "TP_TP") (pintype "input"))
    )
    (net (code "44") (name "Net-(TP169-PadTP)") (class "Default")
      (node (ref "TP169") (pin "TP") (pinfunction "TP_TP") (pintype "input"))
      (node (ref "TP170") (pin "TP") (pinfunction "TP_TP") (pintype "input"))
      (node (ref "TP171") (pin "TP") (pinfunction "TP_TP") (pintype "input"))
      (node (ref "TP172") (pin "TP") (pinfunction "TP_TP") (pintype "input"))
    )
    (net (code "45") (name "Net-(TP173-PadTP)") (class "Default")
      (node (ref "TP173") (pin "TP") (pinfunction "TP_TP") (pintype "input"))
      (node (ref "TP174") (pin "TP") (pinfunction "TP_TP") (pintype "input"))
      (node (ref "TP175") (pin "TP") (pinfunction "TP_TP") (pintype "input"))
      (node (ref "TP176") (pin "TP") (pinfunction "TP_TP") (pintype "input"))
    )
    (net (code "46") (name "Net-(TP177-PadTP)") (class "Default")
      (node (ref "TP177") (pin "TP") (pinfunction "TP_TP") (pintype "input"))
      (node (ref "TP178") (pin "TP") (pinfunction "TP_TP") (pintype "input"))
      (node (ref "TP179") (pin "TP") (pinfunction "TP_TP") (pintype "input"))
      (node (ref "TP180") (pin "TP") (pinfunction "TP_TP") (pintype "input"))
    )
    (net (code "47") (name "Net-(TP181-PadTP)") (class "Default")
      (node (ref "TP181") (pin "TP") (pinfunction "TP_TP") (pintype "input"))
      (node (ref "TP182") (pin "TP") (pinfunction "TP_TP") (pintype "input"))
      (node (ref "TP183") (pin "TP") (pinfunction "TP_TP") (pintype "input"))
      (node (ref "TP184") (pin "TP") (pinfunction "TP_TP") (pintype "input"))
      (node (ref "TP468") (pin "TP") (pinfunction "TP_TP") (pintype "input"))
      (node (ref "TP469") (pin "TP") (pinfunction "TP_TP") (pintype "input"))
    )
    (net (code "48") (name "Net-(TP185-PadTP)") (class "Default")
      (node (ref "TP185") (pin "TP") (pinfunction "TP_TP") (pintype "input"))
      (node (ref "TP186") (pin "TP") (pinfunction "TP_TP") (pintype "input"))
      (node (ref "TP187") (pin "TP") (pinfunction "TP_TP") (pintype "input"))
      (node (ref "TP188") (pin "TP") (pinfunction "TP_TP") (pintype "input"))
      (node (ref "TP466") (pin "TP") (pinfunction "TP_TP") (pintype "input"))
      (node (ref "TP467") (pin "TP") (pinfunction "TP_TP") (pintype "input"))
    )
    (net (code "49") (name "Net-(TP189-PadTP)") (class "Default")
      (node (ref "TP189") (pin "TP") (pinfunction "TP_TP") (pintype "input"))
      (node (ref "TP190") (pin "TP") (pinfunction "TP_TP") (pintype "input"))
      (node (ref "TP191") (pin "TP") (pinfunction "TP_TP") (pintype "input"))
      (node (ref "TP192") (pin "TP") (pinfunction "TP_TP") (pintype "input"))
    )
    (net (code "50") (name "Net-(TP193-PadTP)") (class "Default")
      (node (ref "TP193") (pin "TP") (pinfunction "TP_TP") (pintype "input"))
      (node (ref "TP194") (pin "TP") (pinfunction "TP_TP") (pintype "input"))
      (node (ref "TP195") (pin "TP") (pinfunction "TP_TP") (pintype "input"))
      (node (ref "TP196") (pin "TP") (pinfunction "TP_TP") (pintype "input"))
    )
    (net (code "51") (name "Net-(TP197-PadTP)") (class "Default")
      (node (ref "TP197") (pin "TP") (pinfunction "TP_TP") (pintype "input"))
      (node (ref "TP198") (pin "TP") (pinfunction "TP_TP") (pintype "input"))
      (node (ref "TP199") (pin "TP") (pinfunction "TP_TP") (pintype "input"))
      (node (ref "TP200") (pin "TP") (pinfunction "TP_TP") (pintype "input"))
    )
    (net (code "52") (name "Net-(TP201-PadTP)") (class "Default")
      (node (ref "TP201") (pin "TP") (pinfunction "TP_TP") (pintype "input"))
      (node (ref "TP202") (pin "TP") (pinfunction "TP_TP") (pintype "input"))
      (node (ref "TP203") (pin "TP") (pinfunction "TP_TP") (pintype "input"))
      (node (ref "TP204") (pin "TP") (pinfunction "TP_TP") (pintype "input"))
    )
    (net (code "53") (name "Net-(TP205-PadTP)") (class "Default")
      (node (ref "TP205") (pin "TP") (pinfunction "TP_TP") (pintype "input"))
      (node (ref "TP206") (pin "TP") (pinfunction "TP_TP") (pintype "input"))
      (node (ref "TP207") (pin "TP") (pinfunction "TP_TP") (pintype "input"))
      (node (ref "TP208") (pin "TP") (pinfunction "TP_TP") (pintype "input"))
    )
    (net (code "54") (name "Net-(TP209-PadTP)") (class "Default")
      (node (ref "TP209") (pin "TP") (pinfunction "TP_TP") (pintype "input"))
      (node (ref "TP210") (pin "TP") (pinfunction "TP_TP") (pintype "input"))
      (node (ref "TP211") (pin "TP") (pinfunction "TP_TP") (pintype "input"))
      (node (ref "TP212") (pin "TP") (pinfunction "TP_TP") (pintype "input"))
    )
    (net (code "55") (name "Net-(TP213-PadTP)") (class "Default")
      (node (ref "TP213") (pin "TP") (pinfunction "TP_TP") (pintype "input"))
      (node (ref "TP214") (pin "TP") (pinfunction "TP_TP") (pintype "input"))
      (node (ref "TP215") (pin "TP") (pinfunction "TP_TP") (pintype "input"))
      (node (ref "TP216") (pin "TP") (pinfunction "TP_TP") (pintype "input"))
    )
    (net (code "56") (name "Net-(TP217-PadTP)") (class "Default")
      (node (ref "TP217") (pin "TP") (pinfunction "TP_TP") (pintype "input"))
      (node (ref "TP218") (pin "TP") (pinfunction "TP_TP") (pintype "input"))
      (node (ref "TP219") (pin "TP") (pinfunction "TP_TP") (pintype "input"))
      (node (ref "TP220") (pin "TP") (pinfunction "TP_TP") (pintype "input"))
    )
    (net (code "57") (name "Net-(TP221-PadTP)") (class "Default")
      (node (ref "TP221") (pin "TP") (pinfunction "TP_TP") (pintype "input"))
      (node (ref "TP222") (pin "TP") (pinfunction "TP_TP") (pintype "input"))
      (node (ref "TP223") (pin "TP") (pinfunction "TP_TP") (pintype "input"))
      (node (ref "TP224") (pin "TP") (pinfunction "TP_TP") (pintype "input"))
    )
    (net (code "58") (name "Net-(TP225-PadTP)") (class "Default")
      (node (ref "TP225") (pin "TP") (pinfunction "TP_TP") (pintype "input"))
      (node (ref "TP226") (pin "TP") (pinfunction "TP_TP") (pintype "input"))
      (node (ref "TP227") (pin "TP") (pinfunction "TP_TP") (pintype "input"))
      (node (ref "TP228") (pin "TP") (pinfunction "TP_TP") (pintype "input"))
    )
    (net (code "59") (name "Net-(TP229-PadTP)") (class "Default")
      (node (ref "TP229") (pin "TP") (pinfunction "TP_TP") (pintype "input"))
      (node (ref "TP230") (pin "TP") (pinfunction "TP_TP") (pintype "input"))
      (node (ref "TP231") (pin "TP") (pinfunction "TP_TP") (pintype "input"))
      (node (ref "TP232") (pin "TP") (pinfunction "TP_TP") (pintype "input"))
    )
    (net (code "60") (name "Net-(TP233-PadTP)") (class "Default")
      (node (ref "TP233") (pin "TP") (pinfunction "TP_TP") (pintype "input"))
      (node (ref "TP234") (pin "TP") (pinfunction "TP_TP") (pintype "input"))
      (node (ref "TP235") (pin "TP") (pinfunction "TP_TP") (pintype "input"))
      (node (ref "TP236") (pin "TP") (pinfunction "TP_TP") (pintype "input"))
    )
    (net (code "61") (name "Net-(TP237-PadTP)") (class "Default")
      (node (ref "TP237") (pin "TP") (pinfunction "TP_TP") (pintype "input"))
      (node (ref "TP238") (pin "TP") (pinfunction "TP_TP") (pintype "input"))
      (node (ref "TP239") (pin "TP") (pinfunction "TP_TP") (pintype "input"))
      (node (ref "TP240") (pin "TP") (pinfunction "TP_TP") (pintype "input"))
    )
    (net (code "62") (name "Net-(TP241-PadTP)") (class "Default")
      (node (ref "TP241") (pin "TP") (pinfunction "TP_TP") (pintype "input"))
      (node (ref "TP242") (pin "TP") (pinfunction "TP_TP") (pintype "input"))
      (node (ref "TP243") (pin "TP") (pinfunction "TP_TP") (pintype "input"))
      (node (ref "TP244") (pin "TP") (pinfunction "TP_TP") (pintype "input"))
    )
    (net (code "63") (name "Net-(TP245-PadTP)") (class "Default")
      (node (ref "TP245") (pin "TP") (pinfunction "TP_TP") (pintype "input"))
      (node (ref "TP246") (pin "TP") (pinfunction "TP_TP") (pintype "input"))
      (node (ref "TP247") (pin "TP") (pinfunction "TP_TP") (pintype "input"))
      (node (ref "TP248") (pin "TP") (pinfunction "TP_TP") (pintype "input"))
    )
    (net (code "64") (name "Net-(TP249-PadTP)") (class "Default")
      (node (ref "TP249") (pin "TP") (pinfunction "TP_TP") (pintype "input"))
      (node (ref "TP250") (pin "TP") (pinfunction "TP_TP") (pintype "input"))
      (node (ref "TP251") (pin "TP") (pinfunction "TP_TP") (pintype "input"))
      (node (ref "TP252") (pin "TP") (pinfunction "TP_TP") (pintype "input"))
    )
    (net (code "65") (name "Net-(TP253-PadTP)") (class "Default")
      (node (ref "TP253") (pin "TP") (pinfunction "TP_TP") (pintype "input"))
      (node (ref "TP254") (pin "TP") (pinfunction "TP_TP") (pintype "input"))
      (node (ref "TP255") (pin "TP") (pinfunction "TP_TP") (pintype "input"))
      (node (ref "TP256") (pin "TP") (pinfunction "TP_TP") (pintype "input"))
    )
    (net (code "66") (name "Net-(TP257-PadTP)") (class "Default")
      (node (ref "TP257") (pin "TP") (pinfunction "TP_TP") (pintype "input"))
      (node (ref "TP258") (pin "TP") (pinfunction "TP_TP") (pintype "input"))
      (node (ref "TP259") (pin "TP") (pinfunction "TP_TP") (pintype "input"))
      (node (ref "TP260") (pin "TP") (pinfunction "TP_TP") (pintype "input"))
    )
    (net (code "67") (name "Net-(TP261-PadTP)") (class "Default")
      (node (ref "TP261") (pin "TP") (pinfunction "TP_TP") (pintype "input"))
      (node (ref "TP262") (pin "TP") (pinfunction "TP_TP") (pintype "input"))
      (node (ref "TP263") (pin "TP") (pinfunction "TP_TP") (pintype "input"))
      (node (ref "TP264") (pin "TP") (pinfunction "TP_TP") (pintype "input"))
    )
    (net (code "68") (name "Net-(TP265-PadTP)") (class "Default")
      (node (ref "TP265") (pin "TP") (pinfunction "TP_TP") (pintype "input"))
      (node (ref "TP266") (pin "TP") (pinfunction "TP_TP") (pintype "input"))
      (node (ref "TP267") (pin "TP") (pinfunction "TP_TP") (pintype "input"))
      (node (ref "TP268") (pin "TP") (pinfunction "TP_TP") (pintype "input"))
    )
    (net (code "69") (name "Net-(TP269-PadTP)") (class "Default")
      (node (ref "TP269") (pin "TP") (pinfunction "TP_TP") (pintype "input"))
      (node (ref "TP270") (pin "TP") (pinfunction "TP_TP") (pintype "input"))
      (node (ref "TP271") (pin "TP") (pinfunction "TP_TP") (pintype "input"))
      (node (ref "TP272") (pin "TP") (pinfunction "TP_TP") (pintype "input"))
    )
    (net (code "70") (name "Net-(TP273-PadTP)") (class "Default")
      (node (ref "TP273") (pin "TP") (pinfunction "TP_TP") (pintype "input"))
      (node (ref "TP274") (pin "TP") (pinfunction "TP_TP") (pintype "input"))
      (node (ref "TP275") (pin "TP") (pinfunction "TP_TP") (pintype "input"))
      (node (ref "TP276") (pin "TP") (pinfunction "TP_TP") (pintype "input"))
    )
    (net (code "71") (name "Net-(TP277-PadTP)") (class "Default")
      (node (ref "TP277") (pin "TP") (pinfunction "TP_TP") (pintype "input"))
      (node (ref "TP278") (pin "TP") (pinfunction "TP_TP") (pintype "input"))
      (node (ref "TP279") (pin "TP") (pinfunction "TP_TP") (pintype "input"))
      (node (ref "TP280") (pin "TP") (pinfunction "TP_TP") (pintype "input"))
    )
    (net (code "72") (name "Net-(TP281-PadTP)") (class "Default")
      (node (ref "TP281") (pin "TP") (pinfunction "TP_TP") (pintype "input"))
      (node (ref "TP282") (pin "TP") (pinfunction "TP_TP") (pintype "input"))
      (node (ref "TP283") (pin "TP") (pinfunction "TP_TP") (pintype "input"))
      (node (ref "TP284") (pin "TP") (pinfunction "TP_TP") (pintype "input"))
    )
    (net (code "73") (name "Net-(TP285-PadTP)") (class "Default")
      (node (ref "TP285") (pin "TP") (pinfunction "TP_TP") (pintype "input"))
      (node (ref "TP286") (pin "TP") (pinfunction "TP_TP") (pintype "input"))
      (node (ref "TP287") (pin "TP") (pinfunction "TP_TP") (pintype "input"))
      (node (ref "TP288") (pin "TP") (pinfunction "TP_TP") (pintype "input"))
    )
    (net (code "74") (name "Net-(TP289-PadTP)") (class "Default")
      (node (ref "TP289") (pin "TP") (pinfunction "TP_TP") (pintype "input"))
      (node (ref "TP290") (pin "TP") (pinfunction "TP_TP") (pintype "input"))
      (node (ref "TP291") (pin "TP") (pinfunction "TP_TP") (pintype "input"))
      (node (ref "TP292") (pin "TP") (pinfunction "TP_TP") (pintype "input"))
    )
    (net (code "75") (name "Net-(TP293-PadTP)") (class "Default")
      (node (ref "TP293") (pin "TP") (pinfunction "TP_TP") (pintype "input"))
      (node (ref "TP294") (pin "TP") (pinfunction "TP_TP") (pintype "input"))
      (node (ref "TP295") (pin "TP") (pinfunction "TP_TP") (pintype "input"))
      (node (ref "TP296") (pin "TP") (pinfunction "TP_TP") (pintype "input"))
    )
    (net (code "76") (name "Net-(TP297-PadTP)") (class "Default")
      (node (ref "TP297") (pin "TP") (pinfunction "TP_TP") (pintype "input"))
      (node (ref "TP298") (pin "TP") (pinfunction "TP_TP") (pintype "input"))
      (node (ref "TP299") (pin "TP") (pinfunction "TP_TP") (pintype "input"))
      (node (ref "TP300") (pin "TP") (pinfunction "TP_TP") (pintype "input"))
    )
    (net (code "77") (name "Net-(TP301-PadTP)") (class "Default")
      (node (ref "TP301") (pin "TP") (pinfunction "TP_TP") (pintype "input"))
      (node (ref "TP302") (pin "TP") (pinfunction "TP_TP") (pintype "input"))
      (node (ref "TP303") (pin "TP") (pinfunction "TP_TP") (pintype "input"))
      (node (ref "TP304") (pin "TP") (pinfunction "TP_TP") (pintype "input"))
    )
    (net (code "78") (name "Net-(TP305-PadTP)") (class "Default")
      (node (ref "TP305") (pin "TP") (pinfunction "TP_TP") (pintype "input"))
      (node (ref "TP306") (pin "TP") (pinfunction "TP_TP") (pintype "input"))
      (node (ref "TP307") (pin "TP") (pinfunction "TP_TP") (pintype "input"))
      (node (ref "TP308") (pin "TP") (pinfunction "TP_TP") (pintype "input"))
    )
    (net (code "79") (name "Net-(TP309-PadTP)") (class "Default")
      (node (ref "TP309") (pin "TP") (pinfunction "TP_TP") (pintype "input"))
      (node (ref "TP310") (pin "TP") (pinfunction "TP_TP") (pintype "input"))
      (node (ref "TP311") (pin "TP") (pinfunction "TP_TP") (pintype "input"))
      (node (ref "TP312") (pin "TP") (pinfunction "TP_TP") (pintype "input"))
    )
    (net (code "80") (name "Net-(TP313-PadTP)") (class "Default")
      (node (ref "TP313") (pin "TP") (pinfunction "TP_TP") (pintype "input"))
      (node (ref "TP314") (pin "TP") (pinfunction "TP_TP") (pintype "input"))
      (node (ref "TP315") (pin "TP") (pinfunction "TP_TP") (pintype "input"))
      (node (ref "TP316") (pin "TP") (pinfunction "TP_TP") (pintype "input"))
    )
    (net (code "81") (name "Net-(TP317-PadTP)") (class "Default")
      (node (ref "TP317") (pin "TP") (pinfunction "TP_TP") (pintype "input"))
      (node (ref "TP318") (pin "TP") (pinfunction "TP_TP") (pintype "input"))
      (node (ref "TP319") (pin "TP") (pinfunction "TP_TP") (pintype "input"))
      (node (ref "TP320") (pin "TP") (pinfunction "TP_TP") (pintype "input"))
    )
    (net (code "82") (name "Net-(TP321-PadTP)") (class "Default")
      (node (ref "TP321") (pin "TP") (pinfunction "TP_TP") (pintype "input"))
      (node (ref "TP322") (pin "TP") (pinfunction "TP_TP") (pintype "input"))
      (node (ref "TP323") (pin "TP") (pinfunction "TP_TP") (pintype "input"))
      (node (ref "TP324") (pin "TP") (pinfunction "TP_TP") (pintype "input"))
    )
    (net (code "83") (name "Net-(TP325-PadTP)") (class "Default")
      (node (ref "TP325") (pin "TP") (pinfunction "TP_TP") (pintype "input"))
      (node (ref "TP326") (pin "TP") (pinfunction "TP_TP") (pintype "input"))
      (node (ref "TP327") (pin "TP") (pinfunction "TP_TP") (pintype "input"))
      (node (ref "TP328") (pin "TP") (pinfunction "TP_TP") (pintype "input"))
    )
    (net (code "84") (name "Net-(TP329-PadTP)") (class "Default")
      (node (ref "TP329") (pin "TP") (pinfunction "TP_TP") (pintype "input"))
      (node (ref "TP330") (pin "TP") (pinfunction "TP_TP") (pintype "input"))
      (node (ref "TP331") (pin "TP") (pinfunction "TP_TP") (pintype "input"))
      (node (ref "TP332") (pin "TP") (pinfunction "TP_TP") (pintype "input"))
    )
    (net (code "85") (name "Net-(TP333-PadTP)") (class "Default")
      (node (ref "TP333") (pin "TP") (pinfunction "TP_TP") (pintype "input"))
      (node (ref "TP334") (pin "TP") (pinfunction "TP_TP") (pintype "input"))
      (node (ref "TP335") (pin "TP") (pinfunction "TP_TP") (pintype "input"))
      (node (ref "TP336") (pin "TP") (pinfunction "TP_TP") (pintype "input"))
    )
    (net (code "86") (name "Net-(TP337-PadTP)") (class "Default")
      (node (ref "TP337") (pin "TP") (pinfunction "TP_TP") (pintype "input"))
      (node (ref "TP338") (pin "TP") (pinfunction "TP_TP") (pintype "input"))
      (node (ref "TP339") (pin "TP") (pinfunction "TP_TP") (pintype "input"))
      (node (ref "TP340") (pin "TP") (pinfunction "TP_TP") (pintype "input"))
    )
    (net (code "87") (name "Net-(TP341-PadTP)") (class "Default")
      (node (ref "TP341") (pin "TP") (pinfunction "TP_TP") (pintype "input"))
      (node (ref "TP342") (pin "TP") (pinfunction "TP_TP") (pintype "input"))
      (node (ref "TP343") (pin "TP") (pinfunction "TP_TP") (pintype "input"))
      (node (ref "TP344") (pin "TP") (pinfunction "TP_TP") (pintype "input"))
    )
    (net (code "88") (name "Net-(TP345-PadTP)") (class "Default")
      (node (ref "TP345") (pin "TP") (pinfunction "TP_TP") (pintype "input"))
      (node (ref "TP346") (pin "TP") (pinfunction "TP_TP") (pintype "input"))
      (node (ref "TP347") (pin "TP") (pinfunction "TP_TP") (pintype "input"))
      (node (ref "TP348") (pin "TP") (pinfunction "TP_TP") (pintype "input"))
    )
    (net (code "89") (name "Net-(TP349-PadTP)") (class "Default")
      (node (ref "TP349") (pin "TP") (pinfunction "TP_TP") (pintype "input"))
      (node (ref "TP350") (pin "TP") (pinfunction "TP_TP") (pintype "input"))
      (node (ref "TP351") (pin "TP") (pinfunction "TP_TP") (pintype "input"))
      (node (ref "TP352") (pin "TP") (pinfunction "TP_TP") (pintype "input"))
    )
    (net (code "90") (name "Net-(TP353-PadTP)") (class "Default")
      (node (ref "TP353") (pin "TP") (pinfunction "TP_TP") (pintype "input"))
      (node (ref "TP354") (pin "TP") (pinfunction "TP_TP") (pintype "input"))
      (node (ref "TP355") (pin "TP") (pinfunction "TP_TP") (pintype "input"))
      (node (ref "TP356") (pin "TP") (pinfunction "TP_TP") (pintype "input"))
    )
    (net (code "91") (name "Net-(TP357-PadTP)") (class "Default")
      (node (ref "TP357") (pin "TP") (pinfunction "TP_TP") (pintype "input"))
      (node (ref "TP358") (pin "TP") (pinfunction "TP_TP") (pintype "input"))
      (node (ref "TP359") (pin "TP") (pinfunction "TP_TP") (pintype "input"))
      (node (ref "TP360") (pin "TP") (pinfunction "TP_TP") (pintype "input"))
    )
    (net (code "92") (name "Net-(TP361-PadTP)") (class "Default")
      (node (ref "TP361") (pin "TP") (pinfunction "TP_TP") (pintype "input"))
      (node (ref "TP362") (pin "TP") (pinfunction "TP_TP") (pintype "input"))
      (node (ref "TP363") (pin "TP") (pinfunction "TP_TP") (pintype "input"))
      (node (ref "TP364") (pin "TP") (pinfunction "TP_TP") (pintype "input"))
    )
    (net (code "93") (name "Net-(TP365-PadTP)") (class "Default")
      (node (ref "TP365") (pin "TP") (pinfunction "TP_TP") (pintype "input"))
      (node (ref "TP366") (pin "TP") (pinfunction "TP_TP") (pintype "input"))
      (node (ref "TP367") (pin "TP") (pinfunction "TP_TP") (pintype "input"))
      (node (ref "TP368") (pin "TP") (pinfunction "TP_TP") (pintype "input"))
    )
    (net (code "94") (name "Net-(TP369-PadTP)") (class "Default")
      (node (ref "TP369") (pin "TP") (pinfunction "TP_TP") (pintype "input"))
      (node (ref "TP370") (pin "TP") (pinfunction "TP_TP") (pintype "input"))
      (node (ref "TP371") (pin "TP") (pinfunction "TP_TP") (pintype "input"))
      (node (ref "TP372") (pin "TP") (pinfunction "TP_TP") (pintype "input"))
    )
    (net (code "95") (name "Net-(TP373-PadTP)") (class "Default")
      (node (ref "TP373") (pin "TP") (pinfunction "TP_TP") (pintype "input"))
      (node (ref "TP374") (pin "TP") (pinfunction "TP_TP") (pintype "input"))
      (node (ref "TP375") (pin "TP") (pinfunction "TP_TP") (pintype "input"))
      (node (ref "TP376") (pin "TP") (pinfunction "TP_TP") (pintype "input"))
    )
    (net (code "96") (name "Net-(TP377-PadTP)") (class "Default")
      (node (ref "TP377") (pin "TP") (pinfunction "TP_TP") (pintype "input"))
      (node (ref "TP378") (pin "TP") (pinfunction "TP_TP") (pintype "input"))
      (node (ref "TP379") (pin "TP") (pinfunction "TP_TP") (pintype "input"))
      (node (ref "TP380") (pin "TP") (pinfunction "TP_TP") (pintype "input"))
    )
    (net (code "97") (name "Net-(TP381-PadTP)") (class "Default")
      (node (ref "TP381") (pin "TP") (pinfunction "TP_TP") (pintype "input"))
      (node (ref "TP382") (pin "TP") (pinfunction "TP_TP") (pintype "input"))
      (node (ref "TP383") (pin "TP") (pinfunction "TP_TP") (pintype "input"))
      (node (ref "TP384") (pin "TP") (pinfunction "TP_TP") (pintype "input"))
    )
    (net (code "98") (name "Net-(TP385-PadTP)") (class "Default")
      (node (ref "TP385") (pin "TP") (pinfunction "TP_TP") (pintype "input"))
      (node (ref "TP386") (pin "TP") (pinfunction "TP_TP") (pintype "input"))
      (node (ref "TP387") (pin "TP") (pinfunction "TP_TP") (pintype "input"))
      (node (ref "TP388") (pin "TP") (pinfunction "TP_TP") (pintype "input"))
    )
    (net (code "99") (name "Net-(TP389-PadTP)") (class "Default")
      (node (ref "TP389") (pin "TP") (pinfunction "TP_TP") (pintype "input"))
      (node (ref "TP390") (pin "TP") (pinfunction "TP_TP") (pintype "input"))
      (node (ref "TP391") (pin "TP") (pinfunction "TP_TP") (pintype "input"))
      (node (ref "TP392") (pin "TP") (pinfunction "TP_TP") (pintype "input"))
      (node (ref "TP472") (pin "TP") (pinfunction "TP_TP") (pintype "input"))
      (node (ref "TP473") (pin "TP") (pinfunction "TP_TP") (pintype "input"))
    )
    (net (code "100") (name "Net-(TP393-PadTP)") (class "Default")
      (node (ref "TP393") (pin "TP") (pinfunction "TP_TP") (pintype "input"))
      (node (ref "TP394") (pin "TP") (pinfunction "TP_TP") (pintype "input"))
      (node (ref "TP395") (pin "TP") (pinfunction "TP_TP") (pintype "input"))
      (node (ref "TP396") (pin "TP") (pinfunction "TP_TP") (pintype "input"))
      (node (ref "TP470") (pin "TP") (pinfunction "TP_TP") (pintype "input"))
      (node (ref "TP471") (pin "TP") (pinfunction "TP_TP") (pintype "input"))
    )
    (net (code "101") (name "Net-(TP397-PadTP)") (class "Default")
      (node (ref "TP397") (pin "TP") (pinfunction "TP_TP") (pintype "input"))
      (node (ref "TP398") (pin "TP") (pinfunction "TP_TP") (pintype "input"))
      (node (ref "TP399") (pin "TP") (pinfunction "TP_TP") (pintype "input"))
      (node (ref "TP400") (pin "TP") (pinfunction "TP_TP") (pintype "input"))
    )
    (net (code "102") (name "Net-(TP401-PadTP)") (class "Default")
      (node (ref "TP401") (pin "TP") (pinfunction "TP_TP") (pintype "input"))
      (node (ref "TP402") (pin "TP") (pinfunction "TP_TP") (pintype "input"))
      (node (ref "TP403") (pin "TP") (pinfunction "TP_TP") (pintype "input"))
      (node (ref "TP404") (pin "TP") (pinfunction "TP_TP") (pintype "input"))
      (node (ref "TP405") (pin "TP") (pinfunction "TP_TP") (pintype "input"))
      (node (ref "TP406") (pin "TP") (pinfunction "TP_TP") (pintype "input"))
      (node (ref "TP407") (pin "TP") (pinfunction "TP_TP") (pintype "input"))
      (node (ref "TP408") (pin "TP") (pinfunction "TP_TP") (pintype "input"))
    )
    (net (code "103") (name "Net-(TP409-PadTP)") (class "Default")
      (node (ref "TP409") (pin "TP") (pinfunction "TP_TP") (pintype "input"))
      (node (ref "TP410") (pin "TP") (pinfunction "TP_TP") (pintype "input"))
      (node (ref "TP411") (pin "TP") (pinfunction "TP_TP") (pintype "input"))
    )
    (net (code "104") (name "Net-(TP412-PadTP)") (class "Default")
      (node (ref "TP412") (pin "TP") (pinfunction "TP_TP") (pintype "input"))
      (node (ref "TP413") (pin "TP") (pinfunction "TP_TP") (pintype "input"))
      (node (ref "TP414") (pin "TP") (pinfunction "TP_TP") (pintype "input"))
    )
    (net (code "105") (name "Net-(TP415-PadTP)") (class "Default")
      (node (ref "TP415") (pin "TP") (pinfunction "TP_TP") (pintype "input"))
      (node (ref "TP416") (pin "TP") (pinfunction "TP_TP") (pintype "input"))
      (node (ref "TP417") (pin "TP") (pinfunction "TP_TP") (pintype "input"))
    )
    (net (code "106") (name "Net-(TP418-PadTP)") (class "Default")
      (node (ref "TP418") (pin "TP") (pinfunction "TP_TP") (pintype "input"))
      (node (ref "TP419") (pin "TP") (pinfunction "TP_TP") (pintype "input"))
      (node (ref "TP420") (pin "TP") (pinfunction "TP_TP") (pintype "input"))
    )
    (net (code "107") (name "Net-(TP421-PadTP)") (class "Default")
      (node (ref "TP421") (pin "TP") (pinfunction "TP_TP") (pintype "input"))
      (node (ref "TP422") (pin "TP") (pinfunction "TP_TP") (pintype "input"))
      (node (ref "TP423") (pin "TP") (pinfunction "TP_TP") (pintype "input"))
      (node (ref "TP424") (pin "TP") (pinfunction "TP_TP") (pintype "input"))
    )
    (net (code "108") (name "Net-(TP425-PadTP)") (class "Default")
      (node (ref "TP425") (pin "TP") (pinfunction "TP_TP") (pintype "input"))
      (node (ref "TP426") (pin "TP") (pinfunction "TP_TP") (pintype "input"))
      (node (ref "TP427") (pin "TP") (pinfunction "TP_TP") (pintype "input"))
      (node (ref "TP428") (pin "TP") (pinfunction "TP_TP") (pintype "input"))
      (node (ref "TP429") (pin "TP") (pinfunction "TP_TP") (pintype "input"))
    )
    (net (code "109") (name "Net-(TP430-PadTP)") (class "Default")
      (node (ref "TP430") (pin "TP") (pinfunction "TP_TP") (pintype "input"))
      (node (ref "TP431") (pin "TP") (pinfunction "TP_TP") (pintype "input"))
      (node (ref "TP432") (pin "TP") (pinfunction "TP_TP") (pintype "input"))
      (node (ref "TP433") (pin "TP") (pinfunction "TP_TP") (pintype "input"))
    )
    (net (code "110") (name "Net-(TP434-PadTP)") (class "Default")
      (node (ref "TP434") (pin "TP") (pinfunction "TP_TP") (pintype "input"))
      (node (ref "TP435") (pin "TP") (pinfunction "TP_TP") (pintype "input"))
      (node (ref "TP436") (pin "TP") (pinfunction "TP_TP") (pintype "input"))
      (node (ref "TP437") (pin "TP") (pinfunction "TP_TP") (pintype "input"))
    )
    (net (code "111") (name "Net-(TP438-PadTP)") (class "Default")
      (node (ref "TP438") (pin "TP") (pinfunction "TP_TP") (pintype "input"))
      (node (ref "TP439") (pin "TP") (pinfunction "TP_TP") (pintype "input"))
      (node (ref "TP440") (pin "TP") (pinfunction "TP_TP") (pintype "input"))
      (node (ref "TP441") (pin "TP") (pinfunction "TP_TP") (pintype "input"))
    )
    (net (code "112") (name "Net-(TP442-PadTP)") (class "Default")
      (node (ref "TP442") (pin "TP") (pinfunction "TP_TP") (pintype "input"))
      (node (ref "TP443") (pin "TP") (pinfunction "TP_TP") (pintype "input"))
      (node (ref "TP444") (pin "TP") (pinfunction "TP_TP") (pintype "input"))
      (node (ref "TP445") (pin "TP") (pinfunction "TP_TP") (pintype "input"))
    )
    (net (code "113") (name "Net-(TP446-PadTP)") (class "Default")
      (node (ref "TP446") (pin "TP") (pinfunction "TP_TP") (pintype "input"))
      (node (ref "TP447") (pin "TP") (pinfunction "TP_TP") (pintype "input"))
      (node (ref "TP448") (pin "TP") (pinfunction "TP_TP") (pintype "input"))
      (node (ref "TP449") (pin "TP") (pinfunction "TP_TP") (pintype "input"))
    )
    (net (code "114") (name "Net-(TP450-PadTP)") (class "Default")
      (node (ref "TP450") (pin "TP") (pinfunction "TP_TP") (pintype "input"))
      (node (ref "TP451") (pin "TP") (pinfunction "TP_TP") (pintype "input"))
      (node (ref "TP452") (pin "TP") (pinfunction "TP_TP") (pintype "input"))
      (node (ref "TP453") (pin "TP") (pinfunction "TP_TP") (pintype "input"))
    )
    (net (code "115") (name "Net-(TP454-PadTP)") (class "Default")
      (node (ref "TP454") (pin "TP") (pinfunction "TP_TP") (pintype "input"))
      (node (ref "TP455") (pin "TP") (pinfunction "TP_TP") (pintype "input"))
      (node (ref "TP456") (pin "TP") (pinfunction "TP_TP") (pintype "input"))
    )
    (net (code "116") (name "Net-(TP457-PadTP)") (class "Default")
      (node (ref "TP457") (pin "TP") (pinfunction "TP_TP") (pintype "input"))
      (node (ref "TP458") (pin "TP") (pinfunction "TP_TP") (pintype "input"))
      (node (ref "TP459") (pin "TP") (pinfunction "TP_TP") (pintype "input"))
    )
    (net (code "117") (name "Net-(TP460-PadTP)") (class "Default")
      (node (ref "TP460") (pin "TP") (pinfunction "TP_TP") (pintype "input"))
      (node (ref "TP461") (pin "TP") (pinfunction "TP_TP") (pintype "input"))
      (node (ref "TP462") (pin "TP") (pinfunction "TP_TP") (pintype "input"))
    )
    (net (code "118") (name "Net-(TP463-PadTP)") (class "Default")
      (node (ref "TP463") (pin "TP") (pinfunction "TP_TP") (pintype "input"))
      (node (ref "TP464") (pin "TP") (pinfunction "TP_TP") (pintype "input"))
      (node (ref "TP465") (pin "TP") (pinfunction "TP_TP") (pintype "input"))
    )
    (net (code "119") (name "Net-(U$1A-1)") (class "Default")
      (node (ref "U$1") (pin "A1") (pinfunction "1_A1") (pintype "bidirectional"))
      (node (ref "U$5") (pin "A1") (pinfunction "P$1_A1") (pintype "passive"))
    )
    (net (code "120") (name "Net-(U$1AA-1)") (class "Default")
      (node (ref "U$1") (pin "R1") (pinfunction "1_R1") (pintype "bidirectional"))
      (node (ref "U$5") (pin "R1") (pinfunction "P$1_R1") (pintype "passive"))
    )
    (net (code "121") (name "Net-(U$1AB-1)") (class "Default")
      (node (ref "U$1") (pin "R2") (pinfunction "1_R2") (pintype "bidirectional"))
      (node (ref "U$5") (pin "R2") (pinfunction "P$1_R2") (pintype "passive"))
    )
    (net (code "122") (name "Net-(U$1AC-1)") (class "Default")
      (node (ref "U$1") (pin "S1") (pinfunction "1_S1") (pintype "bidirectional"))
      (node (ref "U$5") (pin "S1") (pinfunction "P$1_S1") (pintype "passive"))
    )
    (net (code "123") (name "Net-(U$1AD-1)") (class "Default")
      (node (ref "U$1") (pin "S2") (pinfunction "1_S2") (pintype "bidirectional"))
      (node (ref "U$5") (pin "S2") (pinfunction "P$1_S2") (pintype "passive"))
    )
    (net (code "124") (name "Net-(U$1AE-1)") (class "Default")
      (node (ref "U$1") (pin "T1") (pinfunction "1_T1") (pintype "bidirectional"))
      (node (ref "U$5") (pin "T1") (pinfunction "P$1_T1") (pintype "passive"))
    )
    (net (code "125") (name "Net-(U$1AF-1)") (class "Default")
      (node (ref "U$1") (pin "T2") (pinfunction "1_T2") (pintype "bidirectional"))
      (node (ref "U$5") (pin "T2") (pinfunction "P$1_T2") (pintype "passive"))
    )
    (net (code "126") (name "Net-(U$1AG-1)") (class "Default")
      (node (ref "U$1") (pin "U1") (pinfunction "1_U1") (pintype "bidirectional"))
      (node (ref "U$5") (pin "U1") (pinfunction "P$1_U1") (pintype "passive"))
    )
    (net (code "127") (name "Net-(U$1AH-1)") (class "Default")
      (node (ref "U$1") (pin "U2") (pinfunction "1_U2") (pintype "bidirectional"))
      (node (ref "U$5") (pin "U2") (pinfunction "P$1_U2") (pintype "passive"))
    )
    (net (code "128") (name "Net-(U$1AI-1)") (class "Default")
      (node (ref "U$1") (pin "V1") (pinfunction "1_V1") (pintype "bidirectional"))
      (node (ref "U$5") (pin "V1") (pinfunction "P$1_V1") (pintype "passive"))
    )
    (net (code "129") (name "Net-(U$1AJ-1)") (class "Default")
      (node (ref "U$1") (pin "V2") (pinfunction "1_V2") (pintype "bidirectional"))
      (node (ref "U$5") (pin "V2") (pinfunction "P$1_V2") (pintype "passive"))
    )
    (net (code "130") (name "Net-(U$1B-1)") (class "Default")
      (node (ref "U$1") (pin "A2") (pinfunction "1_A2") (pintype "bidirectional"))
      (node (ref "U$5") (pin "A2") (pinfunction "P$1_A2") (pintype "passive"))
    )
    (net (code "131") (name "Net-(U$1C-1)") (class "Default")
      (node (ref "U$1") (pin "B1") (pinfunction "1_B1") (pintype "bidirectional"))
      (node (ref "U$5") (pin "B1") (pinfunction "P$1_B1") (pintype "passive"))
    )
    (net (code "132") (name "Net-(U$1D-1)") (class "Default")
      (node (ref "U$1") (pin "B2") (pinfunction "1_B2") (pintype "bidirectional"))
      (node (ref "U$5") (pin "B2") (pinfunction "P$1_B2") (pintype "passive"))
    )
    (net (code "133") (name "Net-(U$1E-1)") (class "Default")
      (node (ref "U$1") (pin "C1") (pinfunction "1_C1") (pintype "bidirectional"))
      (node (ref "U$5") (pin "C1") (pinfunction "P$1_C1") (pintype "passive"))
    )
    (net (code "134") (name "Net-(U$1F-1)") (class "Default")
      (node (ref "U$1") (pin "C2") (pinfunction "1_C2") (pintype "bidirectional"))
      (node (ref "U$5") (pin "C2") (pinfunction "P$1_C2") (pintype "passive"))
    )
    (net (code "135") (name "Net-(U$1G-1)") (class "Default")
      (node (ref "U$1") (pin "D1") (pinfunction "1_D1") (pintype "bidirectional"))
      (node (ref "U$5") (pin "D1") (pinfunction "P$1_D1") (pintype "passive"))
    )
    (net (code "136") (name "Net-(U$1H-1)") (class "Default")
      (node (ref "U$1") (pin "D2") (pinfunction "1_D2") (pintype "bidirectional"))
      (node (ref "U$5") (pin "D2") (pinfunction "P$1_D2") (pintype "passive"))
    )
    (net (code "137") (name "Net-(U$1I-1)") (class "Default")
      (node (ref "U$1") (pin "E1") (pinfunction "1_E1") (pintype "bidirectional"))
      (node (ref "U$5") (pin "E1") (pinfunction "P$1_E1") (pintype "passive"))
    )
    (net (code "138") (name "Net-(U$1J-1)") (class "Default")
      (node (ref "U$1") (pin "E2") (pinfunction "1_E2") (pintype "bidirectional"))
      (node (ref "U$5") (pin "E2") (pinfunction "P$1_E2") (pintype "passive"))
    )
    (net (code "139") (name "Net-(U$1K-1)") (class "Default")
      (node (ref "U$1") (pin "F1") (pinfunction "1_F1") (pintype "bidirectional"))
      (node (ref "U$5") (pin "F1") (pinfunction "P$1_F1") (pintype "passive"))
    )
    (net (code "140") (name "Net-(U$1L-1)") (class "Default")
      (node (ref "U$1") (pin "F2") (pinfunction "1_F2") (pintype "bidirectional"))
      (node (ref "U$5") (pin "F2") (pinfunction "P$1_F2") (pintype "passive"))
    )
    (net (code "141") (name "Net-(U$1M-1)") (class "Default")
      (node (ref "U$1") (pin "H1") (pinfunction "1_H1") (pintype "bidirectional"))
      (node (ref "U$5") (pin "H1") (pinfunction "P$1_H1") (pintype "passive"))
    )
    (net (code "142") (name "Net-(U$1N-1)") (class "Default")
      (node (ref "U$1") (pin "H2") (pinfunction "1_H2") (pintype "bidirectional"))
      (node (ref "U$5") (pin "H2") (pinfunction "P$1_H2") (pintype "passive"))
    )
    (net (code "143") (name "Net-(U$1O-1)") (class "Default")
      (node (ref "U$1") (pin "J1") (pinfunction "1_J1") (pintype "bidirectional"))
      (node (ref "U$5") (pin "J1") (pinfunction "P$1_J1") (pintype "passive"))
    )
    (net (code "144") (name "Net-(U$1P-1)") (class "Default")
      (node (ref "U$1") (pin "J2") (pinfunction "1_J2") (pintype "bidirectional"))
      (node (ref "U$5") (pin "J2") (pinfunction "P$1_J2") (pintype "passive"))
    )
    (net (code "145") (name "Net-(U$1Q-1)") (class "Default")
      (node (ref "U$1") (pin "K1") (pinfunction "1_K1") (pintype "bidirectional"))
      (node (ref "U$5") (pin "K1") (pinfunction "P$1_K1") (pintype "passive"))
    )
    (net (code "146") (name "Net-(U$1R-1)") (class "Default")
      (node (ref "U$1") (pin "K2") (pinfunction "1_K2") (pintype "bidirectional"))
      (node (ref "U$5") (pin "K2") (pinfunction "P$1_K2") (pintype "passive"))
    )
    (net (code "147") (name "Net-(U$1S-1)") (class "Default")
      (node (ref "U$1") (pin "L1") (pinfunction "1_L1") (pintype "bidirectional"))
      (node (ref "U$5") (pin "L1") (pinfunction "P$1_L1") (pintype "passive"))
    )
    (net (code "148") (name "Net-(U$1T-1)") (class "Default")
      (node (ref "U$1") (pin "L2") (pinfunction "1_L2") (pintype "bidirectional"))
      (node (ref "U$5") (pin "L2") (pinfunction "P$1_L2") (pintype "passive"))
    )
    (net (code "149") (name "Net-(U$1U-1)") (class "Default")
      (node (ref "U$1") (pin "M1") (pinfunction "1_M1") (pintype "bidirectional"))
      (node (ref "U$5") (pin "M1") (pinfunction "P$1_M1") (pintype "passive"))
    )
    (net (code "150") (name "Net-(U$1V-1)") (class "Default")
      (node (ref "U$1") (pin "M2") (pinfunction "1_M2") (pintype "bidirectional"))
      (node (ref "U$5") (pin "M2") (pinfunction "P$1_M2") (pintype "passive"))
    )
    (net (code "151") (name "Net-(U$1W-1)") (class "Default")
      (node (ref "U$1") (pin "N1") (pinfunction "1_N1") (pintype "bidirectional"))
      (node (ref "U$5") (pin "N1") (pinfunction "P$1_N1") (pintype "passive"))
    )
    (net (code "152") (name "Net-(U$1X-1)") (class "Default")
      (node (ref "U$1") (pin "N2") (pinfunction "1_N2") (pintype "bidirectional"))
      (node (ref "U$5") (pin "N2") (pinfunction "P$1_N2") (pintype "passive"))
    )
    (net (code "153") (name "Net-(U$1Y-1)") (class "Default")
      (node (ref "U$1") (pin "P1") (pinfunction "1_P1") (pintype "bidirectional"))
      (node (ref "U$5") (pin "P1") (pinfunction "P$1_P1") (pintype "passive"))
    )
    (net (code "154") (name "Net-(U$1Z-1)") (class "Default")
      (node (ref "U$1") (pin "P2") (pinfunction "1_P2") (pintype "bidirectional"))
      (node (ref "U$5") (pin "P2") (pinfunction "P$1_P2") (pintype "passive"))
    )
  )
)
